# PCB-E21-CMB6_v11-16.net
KiCad netlist of a schematic drawn in EAGLE
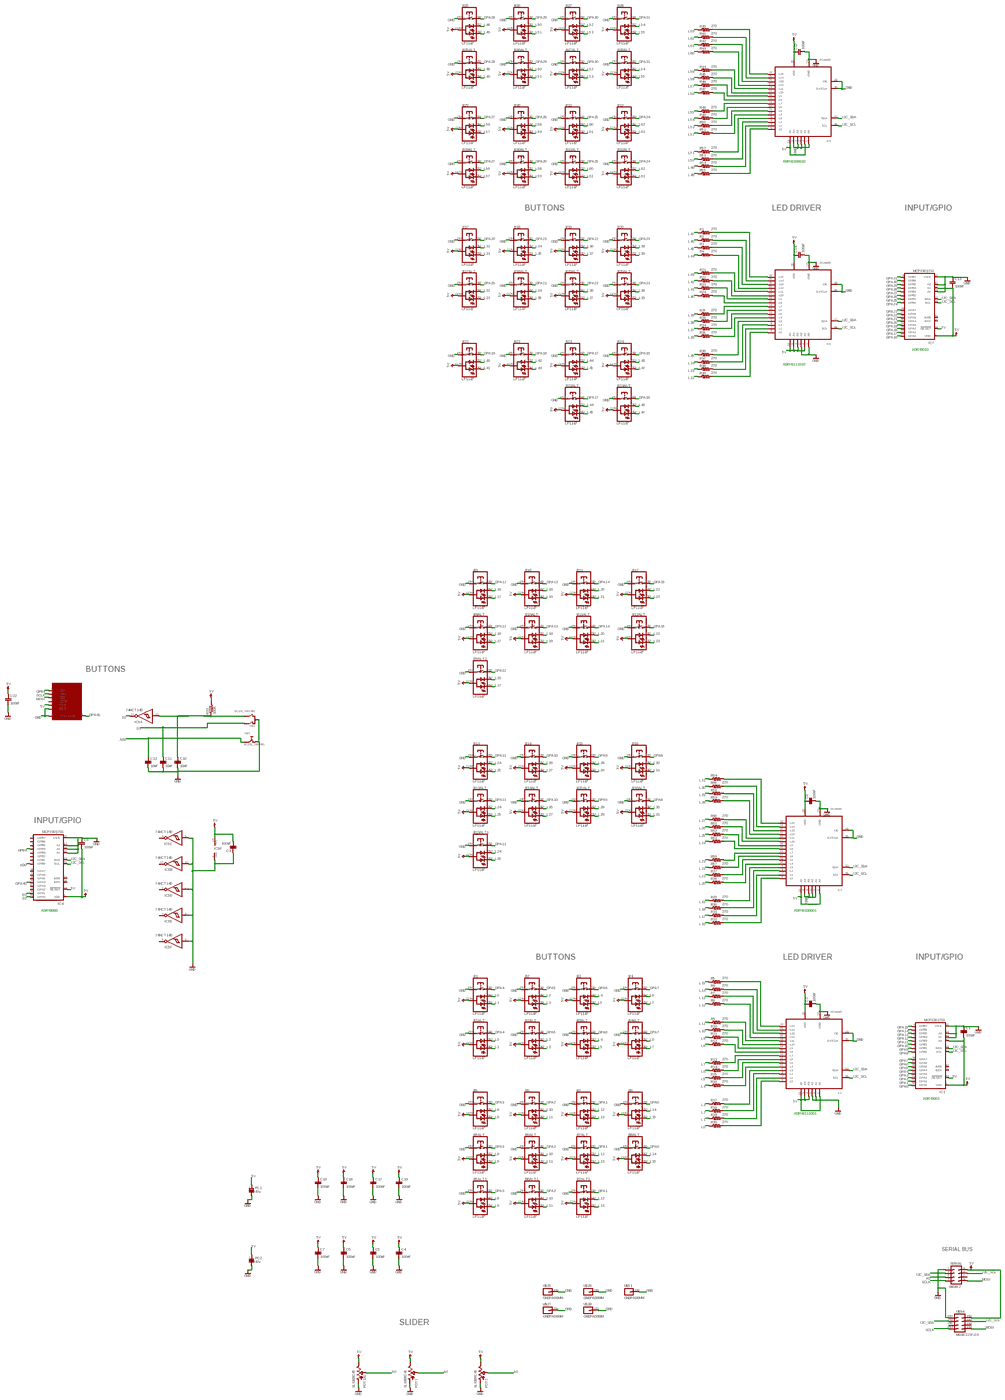
[diagram p0: schematic, sheet 1, overview]
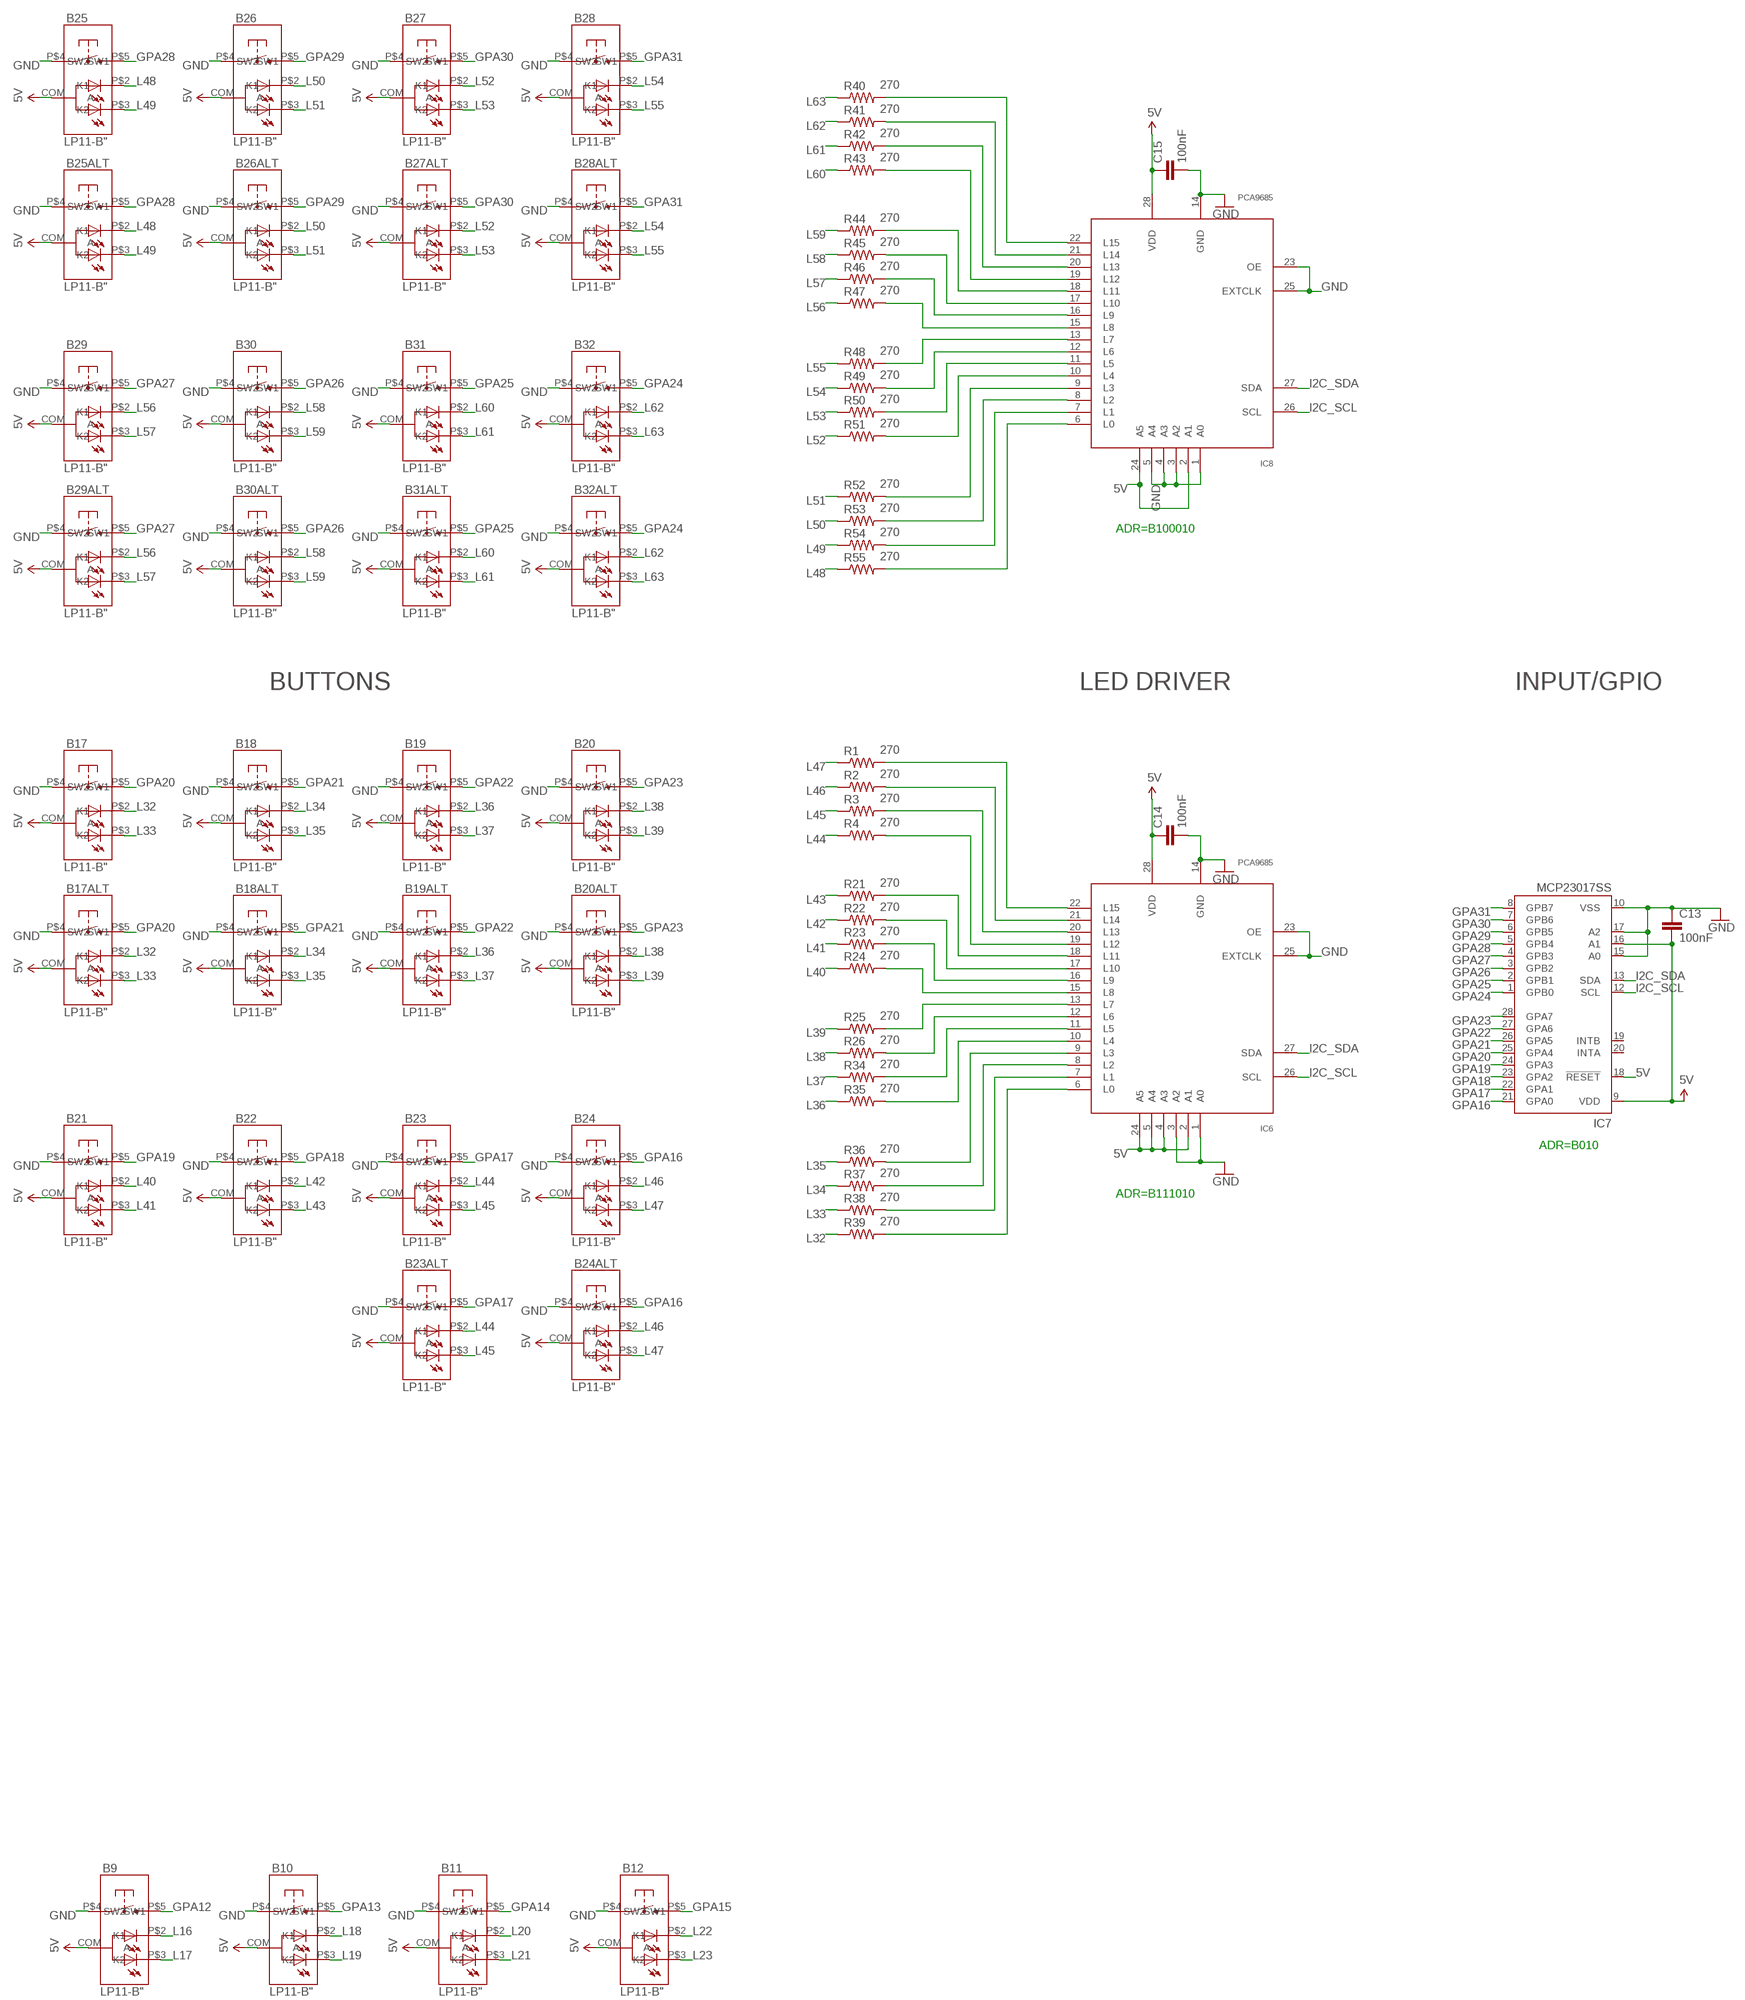
[diagram p1: schematic, sheet 1, part 1 of 5]
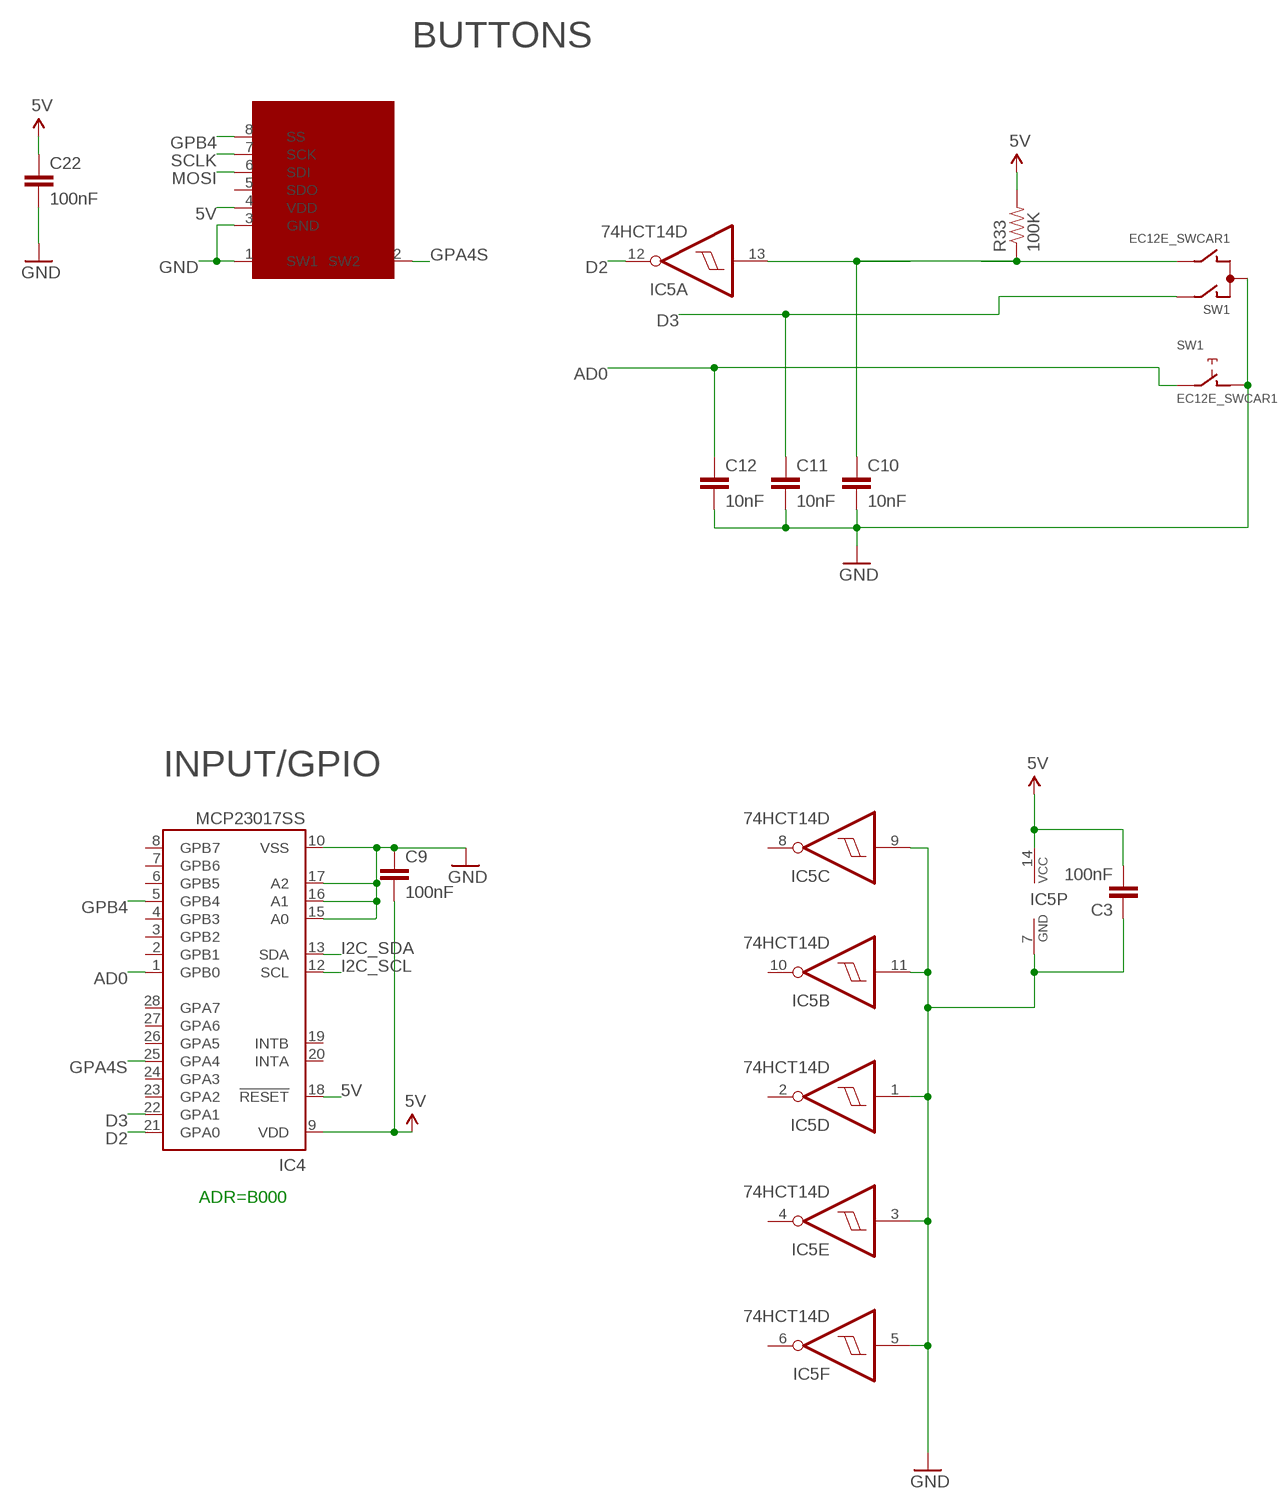
[diagram p2: schematic, sheet 1, part 2 of 5]
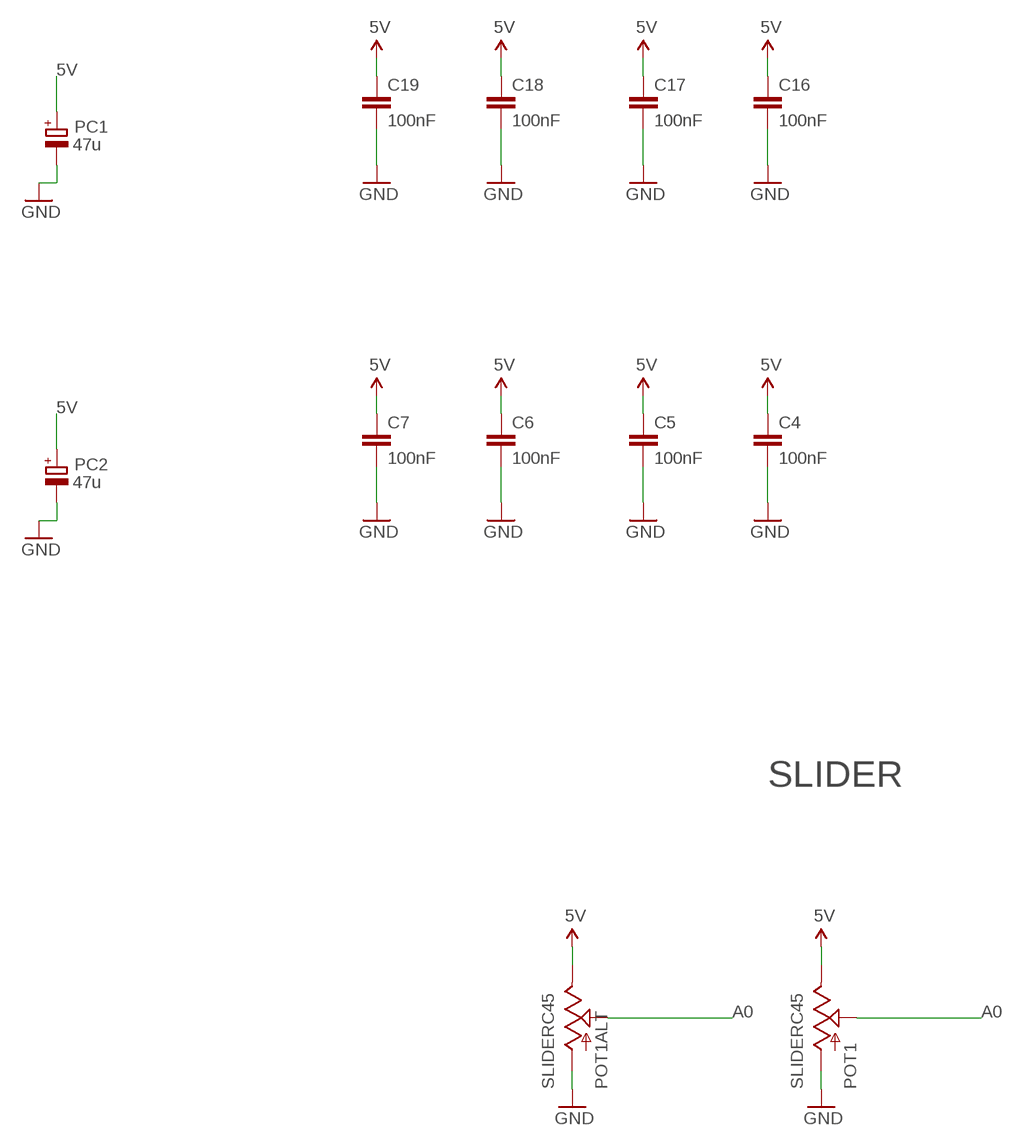
[diagram p3: schematic, sheet 1, part 3 of 5]
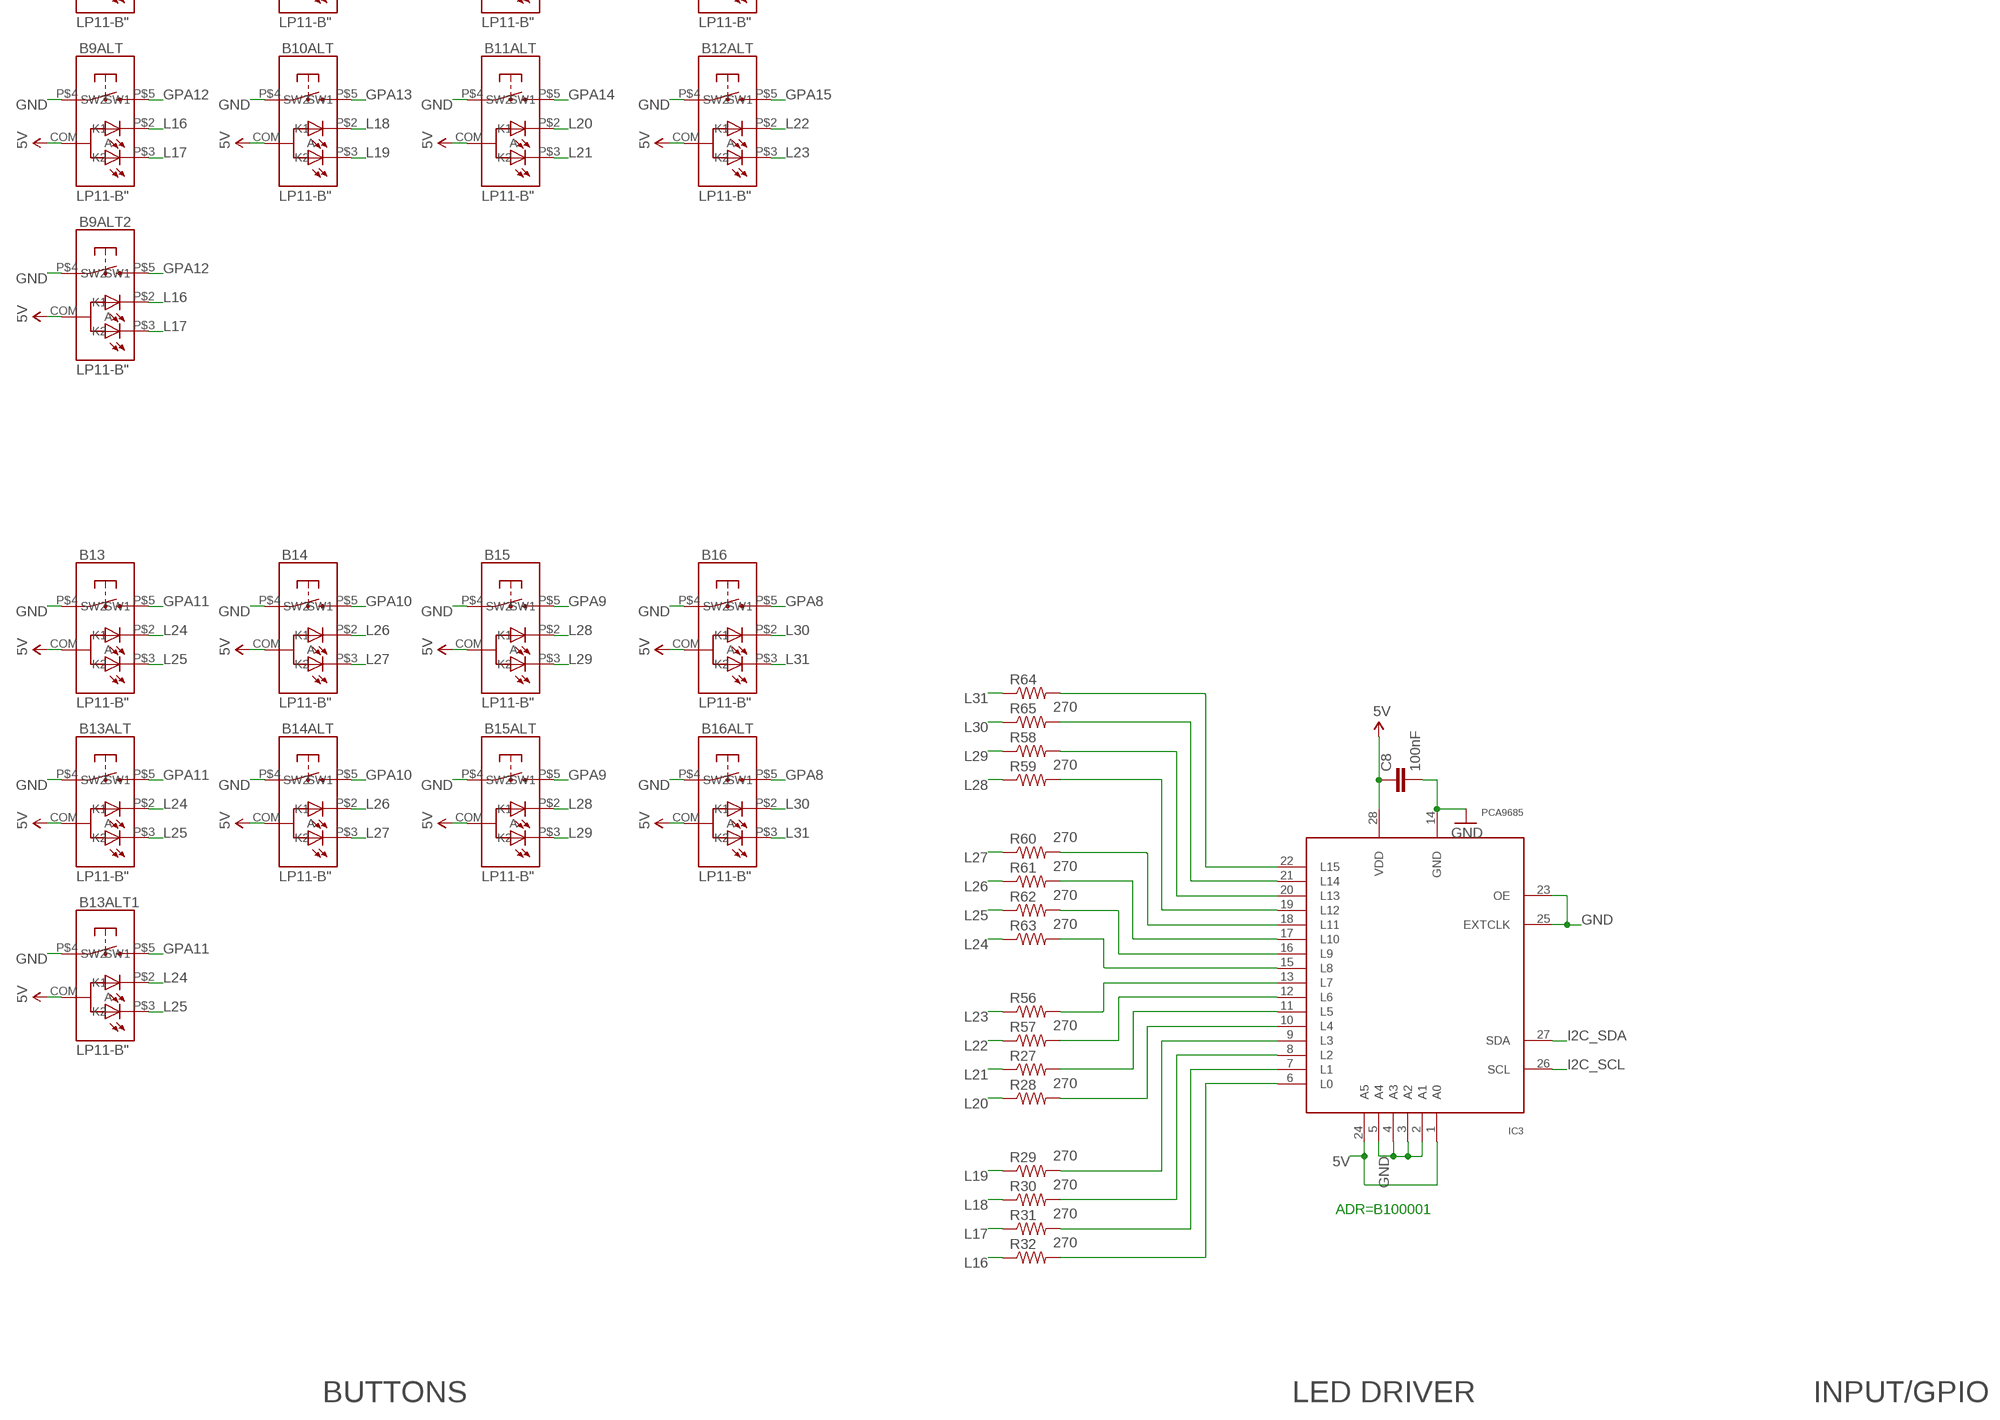
[diagram p4: schematic, sheet 1, part 4 of 5]
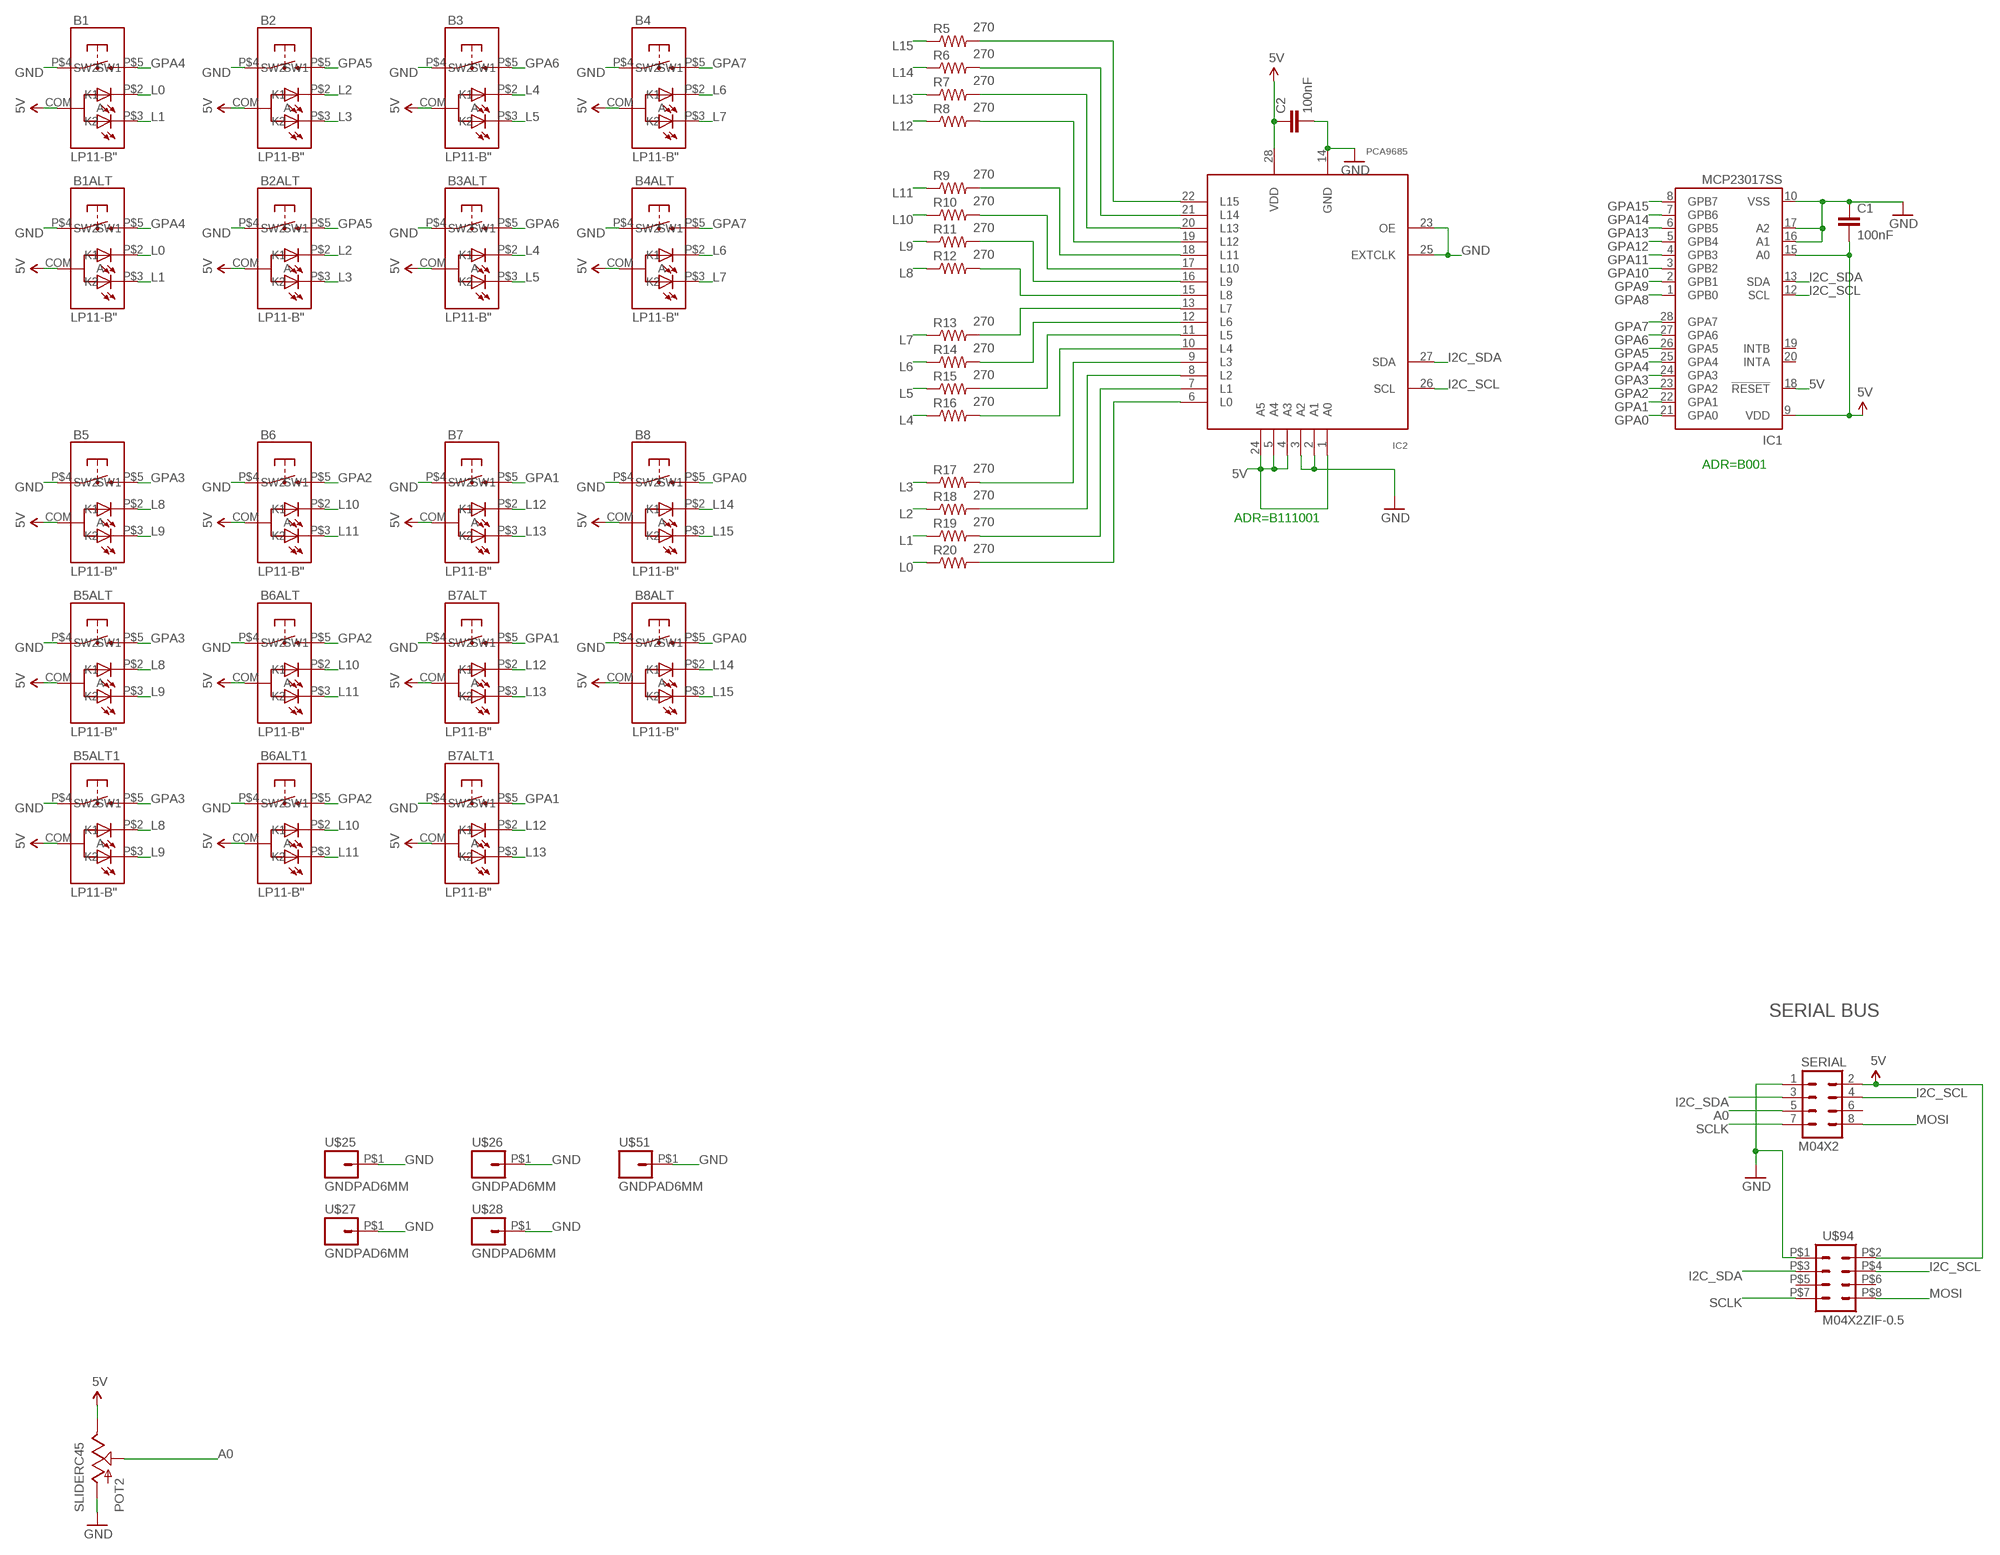
[diagram p5: schematic, sheet 1, part 5 of 5]

(export (version "E")
  (design (tool "Eeschema 10.0.6"))
  (components
    (comp (ref "B1")
      (value "LP11-B\"")
      (footprint "eagle-import:LP11")
      (libsource (lib "eagle-import") (part "LP11-B{dblquote}"))
    )
    (comp (ref "B1ALT")
      (value "LP11-B\"")
      (footprint "eagle-import:LP11")
      (libsource (lib "eagle-import") (part "LP11-B{dblquote}"))
    )
    (comp (ref "B2")
      (value "LP11-B\"")
      (footprint "eagle-import:LP11")
      (libsource (lib "eagle-import") (part "LP11-B{dblquote}"))
    )
    (comp (ref "B2ALT")
      (value "LP11-B\"")
      (footprint "eagle-import:LP11")
      (libsource (lib "eagle-import") (part "LP11-B{dblquote}"))
    )
    (comp (ref "B3")
      (value "LP11-B\"")
      (footprint "eagle-import:LP11")
      (libsource (lib "eagle-import") (part "LP11-B{dblquote}"))
    )
    (comp (ref "B3ALT")
      (value "LP11-B\"")
      (footprint "eagle-import:LP11")
      (libsource (lib "eagle-import") (part "LP11-B{dblquote}"))
    )
    (comp (ref "B4")
      (value "LP11-B\"")
      (footprint "eagle-import:LP11")
      (libsource (lib "eagle-import") (part "LP11-B{dblquote}"))
    )
    (comp (ref "B4ALT")
      (value "LP11-B\"")
      (footprint "eagle-import:LP11")
      (libsource (lib "eagle-import") (part "LP11-B{dblquote}"))
    )
    (comp (ref "B5")
      (value "LP11-B\"")
      (footprint "eagle-import:LP11")
      (libsource (lib "eagle-import") (part "LP11-B{dblquote}"))
    )
    (comp (ref "B5ALT")
      (value "LP11-B\"")
      (footprint "eagle-import:LP11")
      (libsource (lib "eagle-import") (part "LP11-B{dblquote}"))
    )
    (comp (ref "B5ALT1")
      (value "LP11-B\"")
      (footprint "eagle-import:LP11")
      (libsource (lib "eagle-import") (part "LP11-B{dblquote}"))
    )
    (comp (ref "B6")
      (value "LP11-B\"")
      (footprint "eagle-import:LP11")
      (libsource (lib "eagle-import") (part "LP11-B{dblquote}"))
    )
    (comp (ref "B6ALT")
      (value "LP11-B\"")
      (footprint "eagle-import:LP11")
      (libsource (lib "eagle-import") (part "LP11-B{dblquote}"))
    )
    (comp (ref "B6ALT1")
      (value "LP11-B\"")
      (footprint "eagle-import:LP11")
      (libsource (lib "eagle-import") (part "LP11-B{dblquote}"))
    )
    (comp (ref "B7")
      (value "LP11-B\"")
      (footprint "eagle-import:LP11")
      (libsource (lib "eagle-import") (part "LP11-B{dblquote}"))
    )
    (comp (ref "B7ALT")
      (value "LP11-B\"")
      (footprint "eagle-import:LP11")
      (libsource (lib "eagle-import") (part "LP11-B{dblquote}"))
    )
    (comp (ref "B7ALT1")
      (value "LP11-B\"")
      (footprint "eagle-import:LP11")
      (libsource (lib "eagle-import") (part "LP11-B{dblquote}"))
    )
    (comp (ref "B8")
      (value "LP11-B\"")
      (footprint "eagle-import:LP11")
      (libsource (lib "eagle-import") (part "LP11-B{dblquote}"))
    )
    (comp (ref "B8ALT")
      (value "LP11-B\"")
      (footprint "eagle-import:LP11")
      (libsource (lib "eagle-import") (part "LP11-B{dblquote}"))
    )
    (comp (ref "B9")
      (value "LP11-B\"")
      (footprint "eagle-import:LP11")
      (libsource (lib "eagle-import") (part "LP11-B{dblquote}"))
    )
    (comp (ref "B9ALT")
      (value "LP11-B\"")
      (footprint "eagle-import:LP11")
      (libsource (lib "eagle-import") (part "LP11-B{dblquote}"))
    )
    (comp (ref "B9ALT2")
      (value "LP11-B\"")
      (footprint "eagle-import:LP11")
      (libsource (lib "eagle-import") (part "LP11-B{dblquote}"))
    )
    (comp (ref "B10")
      (value "LP11-B\"")
      (footprint "eagle-import:LP11")
      (libsource (lib "eagle-import") (part "LP11-B{dblquote}"))
    )
    (comp (ref "B10ALT")
      (value "LP11-B\"")
      (footprint "eagle-import:LP11")
      (libsource (lib "eagle-import") (part "LP11-B{dblquote}"))
    )
    (comp (ref "B11")
      (value "LP11-B\"")
      (footprint "eagle-import:LP11")
      (libsource (lib "eagle-import") (part "LP11-B{dblquote}"))
    )
    (comp (ref "B11ALT")
      (value "LP11-B\"")
      (footprint "eagle-import:LP11")
      (libsource (lib "eagle-import") (part "LP11-B{dblquote}"))
    )
    (comp (ref "B12")
      (value "LP11-B\"")
      (footprint "eagle-import:LP11")
      (libsource (lib "eagle-import") (part "LP11-B{dblquote}"))
    )
    (comp (ref "B12ALT")
      (value "LP11-B\"")
      (footprint "eagle-import:LP11")
      (libsource (lib "eagle-import") (part "LP11-B{dblquote}"))
    )
    (comp (ref "B13")
      (value "LP11-B\"")
      (footprint "eagle-import:LP11")
      (libsource (lib "eagle-import") (part "LP11-B{dblquote}"))
    )
    (comp (ref "B13ALT")
      (value "LP11-B\"")
      (footprint "eagle-import:LP11")
      (libsource (lib "eagle-import") (part "LP11-B{dblquote}"))
    )
    (comp (ref "B13ALT1")
      (value "LP11-B\"")
      (footprint "eagle-import:LP11")
      (libsource (lib "eagle-import") (part "LP11-B{dblquote}"))
    )
    (comp (ref "B14")
      (value "LP11-B\"")
      (footprint "eagle-import:LP11")
      (libsource (lib "eagle-import") (part "LP11-B{dblquote}"))
    )
    (comp (ref "B14ALT")
      (value "LP11-B\"")
      (footprint "eagle-import:LP11")
      (libsource (lib "eagle-import") (part "LP11-B{dblquote}"))
    )
    (comp (ref "B15")
      (value "LP11-B\"")
      (footprint "eagle-import:LP11")
      (libsource (lib "eagle-import") (part "LP11-B{dblquote}"))
    )
    (comp (ref "B15ALT")
      (value "LP11-B\"")
      (footprint "eagle-import:LP11")
      (libsource (lib "eagle-import") (part "LP11-B{dblquote}"))
    )
    (comp (ref "B16")
      (value "LP11-B\"")
      (footprint "eagle-import:LP11")
      (libsource (lib "eagle-import") (part "LP11-B{dblquote}"))
    )
    (comp (ref "B16ALT")
      (value "LP11-B\"")
      (footprint "eagle-import:LP11")
      (libsource (lib "eagle-import") (part "LP11-B{dblquote}"))
    )
    (comp (ref "B17")
      (value "LP11-B\"")
      (footprint "eagle-import:LP11")
      (libsource (lib "eagle-import") (part "LP11-B{dblquote}"))
    )
    (comp (ref "B17ALT")
      (value "LP11-B\"")
      (footprint "eagle-import:LP11")
      (libsource (lib "eagle-import") (part "LP11-B{dblquote}"))
    )
    (comp (ref "B18")
      (value "LP11-B\"")
      (footprint "eagle-import:LP11")
      (libsource (lib "eagle-import") (part "LP11-B{dblquote}"))
    )
    (comp (ref "B18ALT")
      (value "LP11-B\"")
      (footprint "eagle-import:LP11")
      (libsource (lib "eagle-import") (part "LP11-B{dblquote}"))
    )
    (comp (ref "B19")
      (value "LP11-B\"")
      (footprint "eagle-import:LP11")
      (libsource (lib "eagle-import") (part "LP11-B{dblquote}"))
    )
    (comp (ref "B19ALT")
      (value "LP11-B\"")
      (footprint "eagle-import:LP11")
      (libsource (lib "eagle-import") (part "LP11-B{dblquote}"))
    )
    (comp (ref "B20")
      (value "LP11-B\"")
      (footprint "eagle-import:LP11")
      (libsource (lib "eagle-import") (part "LP11-B{dblquote}"))
    )
    (comp (ref "B20ALT")
      (value "LP11-B\"")
      (footprint "eagle-import:LP11")
      (libsource (lib "eagle-import") (part "LP11-B{dblquote}"))
    )
    (comp (ref "B21")
      (value "LP11-B\"")
      (footprint "eagle-import:LP11")
      (libsource (lib "eagle-import") (part "LP11-B{dblquote}"))
    )
    (comp (ref "B22")
      (value "LP11-B\"")
      (footprint "eagle-import:LP11")
      (libsource (lib "eagle-import") (part "LP11-B{dblquote}"))
    )
    (comp (ref "B23")
      (value "LP11-B\"")
      (footprint "eagle-import:LP11")
      (libsource (lib "eagle-import") (part "LP11-B{dblquote}"))
    )
    (comp (ref "B23ALT")
      (value "LP11-B\"")
      (footprint "eagle-import:LP11")
      (libsource (lib "eagle-import") (part "LP11-B{dblquote}"))
    )
    (comp (ref "B24")
      (value "LP11-B\"")
      (footprint "eagle-import:LP11")
      (libsource (lib "eagle-import") (part "LP11-B{dblquote}"))
    )
    (comp (ref "B24ALT")
      (value "LP11-B\"")
      (footprint "eagle-import:LP11")
      (libsource (lib "eagle-import") (part "LP11-B{dblquote}"))
    )
    (comp (ref "B25")
      (value "LP11-B\"")
      (footprint "eagle-import:LP11")
      (libsource (lib "eagle-import") (part "LP11-B{dblquote}"))
    )
    (comp (ref "B25ALT")
      (value "LP11-B\"")
      (footprint "eagle-import:LP11")
      (libsource (lib "eagle-import") (part "LP11-B{dblquote}"))
    )
    (comp (ref "B26")
      (value "LP11-B\"")
      (footprint "eagle-import:LP11")
      (libsource (lib "eagle-import") (part "LP11-B{dblquote}"))
    )
    (comp (ref "B26ALT")
      (value "LP11-B\"")
      (footprint "eagle-import:LP11")
      (libsource (lib "eagle-import") (part "LP11-B{dblquote}"))
    )
    (comp (ref "B27")
      (value "LP11-B\"")
      (footprint "eagle-import:LP11")
      (libsource (lib "eagle-import") (part "LP11-B{dblquote}"))
    )
    (comp (ref "B27ALT")
      (value "LP11-B\"")
      (footprint "eagle-import:LP11")
      (libsource (lib "eagle-import") (part "LP11-B{dblquote}"))
    )
    (comp (ref "B28")
      (value "LP11-B\"")
      (footprint "eagle-import:LP11")
      (libsource (lib "eagle-import") (part "LP11-B{dblquote}"))
    )
    (comp (ref "B28ALT")
      (value "LP11-B\"")
      (footprint "eagle-import:LP11")
      (libsource (lib "eagle-import") (part "LP11-B{dblquote}"))
    )
    (comp (ref "B29")
      (value "LP11-B\"")
      (footprint "eagle-import:LP11")
      (libsource (lib "eagle-import") (part "LP11-B{dblquote}"))
    )
    (comp (ref "B29ALT")
      (value "LP11-B\"")
      (footprint "eagle-import:LP11")
      (libsource (lib "eagle-import") (part "LP11-B{dblquote}"))
    )
    (comp (ref "B30")
      (value "LP11-B\"")
      (footprint "eagle-import:LP11")
      (libsource (lib "eagle-import") (part "LP11-B{dblquote}"))
    )
    (comp (ref "B30ALT")
      (value "LP11-B\"")
      (footprint "eagle-import:LP11")
      (libsource (lib "eagle-import") (part "LP11-B{dblquote}"))
    )
    (comp (ref "B31")
      (value "LP11-B\"")
      (footprint "eagle-import:LP11")
      (libsource (lib "eagle-import") (part "LP11-B{dblquote}"))
    )
    (comp (ref "B31ALT")
      (value "LP11-B\"")
      (footprint "eagle-import:LP11")
      (libsource (lib "eagle-import") (part "LP11-B{dblquote}"))
    )
    (comp (ref "B32")
      (value "LP11-B\"")
      (footprint "eagle-import:LP11")
      (libsource (lib "eagle-import") (part "LP11-B{dblquote}"))
    )
    (comp (ref "B32ALT")
      (value "LP11-B\"")
      (footprint "eagle-import:LP11")
      (libsource (lib "eagle-import") (part "LP11-B{dblquote}"))
    )
    (comp (ref "C1")
      (value "100nF")
      (footprint "eagle-import:0603-CAP")
      (libsource (lib "eagle-import") (part "CAP0603-CAP"))
    )
    (comp (ref "C2")
      (value "100nF")
      (footprint "eagle-import:0603-CAP")
      (libsource (lib "eagle-import") (part "CAP0603-CAP"))
    )
    (comp (ref "C3")
      (value "100nF")
      (footprint "eagle-import:0603-CAP")
      (libsource (lib "eagle-import") (part "CAP0603-CAP"))
    )
    (comp (ref "C4")
      (value "100nF")
      (footprint "eagle-import:0603-CAP")
      (libsource (lib "eagle-import") (part "CAP0603-CAP"))
    )
    (comp (ref "C5")
      (value "100nF")
      (footprint "eagle-import:0603-CAP")
      (libsource (lib "eagle-import") (part "CAP0603-CAP"))
    )
    (comp (ref "C6")
      (value "100nF")
      (footprint "eagle-import:0603-CAP")
      (libsource (lib "eagle-import") (part "CAP0603-CAP"))
    )
    (comp (ref "C7")
      (value "100nF")
      (footprint "eagle-import:0603-CAP")
      (libsource (lib "eagle-import") (part "CAP0603-CAP"))
    )
    (comp (ref "C8")
      (value "100nF")
      (footprint "eagle-import:0603-CAP")
      (libsource (lib "eagle-import") (part "CAP0603-CAP"))
    )
    (comp (ref "C9")
      (value "100nF")
      (footprint "eagle-import:0603-CAP")
      (libsource (lib "eagle-import") (part "CAP0603-CAP"))
    )
    (comp (ref "C10")
      (value "10nF")
      (footprint "eagle-import:0603-CAP")
      (libsource (lib "eagle-import") (part "CAP0603-CAP"))
    )
    (comp (ref "C11")
      (value "10nF")
      (footprint "eagle-import:0603-CAP")
      (libsource (lib "eagle-import") (part "CAP0603-CAP"))
    )
    (comp (ref "C12")
      (value "10nF")
      (footprint "eagle-import:0603-CAP")
      (libsource (lib "eagle-import") (part "CAP0603-CAP"))
    )
    (comp (ref "C13")
      (value "100nF")
      (footprint "eagle-import:0603-CAP")
      (libsource (lib "eagle-import") (part "CAP0603-CAP"))
    )
    (comp (ref "C14")
      (value "100nF")
      (footprint "eagle-import:0603-CAP")
      (libsource (lib "eagle-import") (part "CAP0603-CAP"))
    )
    (comp (ref "C15")
      (value "100nF")
      (footprint "eagle-import:0603-CAP")
      (libsource (lib "eagle-import") (part "CAP0603-CAP"))
    )
    (comp (ref "C16")
      (value "100nF")
      (footprint "eagle-import:0603-CAP")
      (libsource (lib "eagle-import") (part "CAP0603-CAP"))
    )
    (comp (ref "C17")
      (value "100nF")
      (footprint "eagle-import:0603-CAP")
      (libsource (lib "eagle-import") (part "CAP0603-CAP"))
    )
    (comp (ref "C18")
      (value "100nF")
      (footprint "eagle-import:0603-CAP")
      (libsource (lib "eagle-import") (part "CAP0603-CAP"))
    )
    (comp (ref "C19")
      (value "100nF")
      (footprint "eagle-import:0603-CAP")
      (libsource (lib "eagle-import") (part "CAP0603-CAP"))
    )
    (comp (ref "C22")
      (value "100nF")
      (footprint "eagle-import:0603-CAP")
      (libsource (lib "eagle-import") (part "CAP0603-CAP"))
    )
    (comp (ref "IC1")
      (value "MCP23017SS")
      (footprint "eagle-import:SSOP28")
      (fields
        (field (name "MF") "MICROCHIP")
        (field (name "MPN") "MCP23017-E/SS")
        (field (name "MPN_1") "MCP23017-E/SS")
        (field (name "OC_FARNELL") "1467674")
        (field (name "OC_NEWARK") "31K2960")
      )
      (libsource (lib "eagle-import") (part "MCP23017SS"))
    )
    (comp (ref "IC2")
      (value "PCA9685")
      (footprint "eagle-import:TSSOP28")
      (libsource (lib "eagle-import") (part "PCA9685"))
    )
    (comp (ref "IC3")
      (value "PCA9685")
      (footprint "eagle-import:TSSOP28")
      (libsource (lib "eagle-import") (part "PCA9685"))
    )
    (comp (ref "IC4")
      (value "MCP23017SS")
      (footprint "eagle-import:SSOP28")
      (fields
        (field (name "MF") "MICROCHIP")
        (field (name "MPN") "MCP23017-E/SS")
        (field (name "MPN_1") "MCP23017-E/SS")
        (field (name "OC_FARNELL") "1467674")
        (field (name "OC_NEWARK") "31K2960")
      )
      (libsource (lib "eagle-import") (part "MCP23017SS"))
    )
    (comp (ref "IC5")
      (value "74HCT14D")
      (footprint "eagle-import:SO14")
      (libsource (lib "eagle-import") (part "7414DHCT"))
    )
    (comp (ref "IC6")
      (value "PCA9685")
      (footprint "eagle-import:TSSOP28")
      (libsource (lib "eagle-import") (part "PCA9685"))
    )
    (comp (ref "IC7")
      (value "MCP23017SS")
      (footprint "eagle-import:SSOP28")
      (fields
        (field (name "MF") "MICROCHIP")
        (field (name "MPN") "MCP23017-E/SS")
        (field (name "MPN_1") "MCP23017-E/SS")
        (field (name "OC_FARNELL") "1467674")
        (field (name "OC_NEWARK") "31K2960")
      )
      (libsource (lib "eagle-import") (part "MCP23017SS"))
    )
    (comp (ref "IC8")
      (value "PCA9685")
      (footprint "eagle-import:TSSOP28")
      (libsource (lib "eagle-import") (part "PCA9685"))
    )
    (comp (ref "PC1")
      (value "47u")
      (footprint "eagle-import:PANASONIC_D")
      (libsource (lib "eagle-import") (part "CPOL-EUD"))
    )
    (comp (ref "PC2")
      (value "47u")
      (footprint "eagle-import:PANASONIC_D")
      (libsource (lib "eagle-import") (part "CPOL-EUD"))
    )
    (comp (ref "POT1")
      (value "SLIDERC45")
      (footprint "eagle-import:SLIDER45-CAR1")
      (libsource (lib "eagle-import") (part "SLIDERC45"))
    )
    (comp (ref "POT1ALT")
      (value "SLIDERC45")
      (footprint "eagle-import:SLIDER45-CAR1")
      (libsource (lib "eagle-import") (part "SLIDERC45"))
    )
    (comp (ref "POT2")
      (value "SLIDERC45")
      (footprint "eagle-import:SLIDER45-CAR1")
      (libsource (lib "eagle-import") (part "SLIDERC45"))
    )
    (comp (ref "R1")
      (value "270")
      (footprint "eagle-import:0603-RES")
      (libsource (lib "eagle-import") (part "RESISTOR0603-RES"))
    )
    (comp (ref "R2")
      (value "270")
      (footprint "eagle-import:0603-RES")
      (libsource (lib "eagle-import") (part "RESISTOR0603-RES"))
    )
    (comp (ref "R3")
      (value "270")
      (footprint "eagle-import:0603-RES")
      (libsource (lib "eagle-import") (part "RESISTOR0603-RES"))
    )
    (comp (ref "R4")
      (value "270")
      (footprint "eagle-import:0603-RES")
      (libsource (lib "eagle-import") (part "RESISTOR0603-RES"))
    )
    (comp (ref "R5")
      (value "270")
      (footprint "eagle-import:0603-RES")
      (libsource (lib "eagle-import") (part "RESISTOR0603-RES"))
    )
    (comp (ref "R6")
      (value "270")
      (footprint "eagle-import:0603-RES")
      (libsource (lib "eagle-import") (part "RESISTOR0603-RES"))
    )
    (comp (ref "R7")
      (value "270")
      (footprint "eagle-import:0603-RES")
      (libsource (lib "eagle-import") (part "RESISTOR0603-RES"))
    )
    (comp (ref "R8")
      (value "270")
      (footprint "eagle-import:0603-RES")
      (libsource (lib "eagle-import") (part "RESISTOR0603-RES"))
    )
    (comp (ref "R9")
      (value "270")
      (footprint "eagle-import:0603-RES")
      (libsource (lib "eagle-import") (part "RESISTOR0603-RES"))
    )
    (comp (ref "R10")
      (value "270")
      (footprint "eagle-import:0603-RES")
      (libsource (lib "eagle-import") (part "RESISTOR0603-RES"))
    )
    (comp (ref "R11")
      (value "270")
      (footprint "eagle-import:0603-RES")
      (libsource (lib "eagle-import") (part "RESISTOR0603-RES"))
    )
    (comp (ref "R12")
      (value "270")
      (footprint "eagle-import:0603-RES")
      (libsource (lib "eagle-import") (part "RESISTOR0603-RES"))
    )
    (comp (ref "R13")
      (value "270")
      (footprint "eagle-import:0603-RES")
      (libsource (lib "eagle-import") (part "RESISTOR0603-RES"))
    )
    (comp (ref "R14")
      (value "270")
      (footprint "eagle-import:0603-RES")
      (libsource (lib "eagle-import") (part "RESISTOR0603-RES"))
    )
    (comp (ref "R15")
      (value "270")
      (footprint "eagle-import:0603-RES")
      (libsource (lib "eagle-import") (part "RESISTOR0603-RES"))
    )
    (comp (ref "R16")
      (value "270")
      (footprint "eagle-import:0603-RES")
      (libsource (lib "eagle-import") (part "RESISTOR0603-RES"))
    )
    (comp (ref "R17")
      (value "270")
      (footprint "eagle-import:0603-RES")
      (libsource (lib "eagle-import") (part "RESISTOR0603-RES"))
    )
    (comp (ref "R18")
      (value "270")
      (footprint "eagle-import:0603-RES")
      (libsource (lib "eagle-import") (part "RESISTOR0603-RES"))
    )
    (comp (ref "R19")
      (value "270")
      (footprint "eagle-import:0603-RES")
      (libsource (lib "eagle-import") (part "RESISTOR0603-RES"))
    )
    (comp (ref "R20")
      (value "270")
      (footprint "eagle-import:0603-RES")
      (libsource (lib "eagle-import") (part "RESISTOR0603-RES"))
    )
    (comp (ref "R21")
      (value "270")
      (footprint "eagle-import:0603-RES")
      (libsource (lib "eagle-import") (part "RESISTOR0603-RES"))
    )
    (comp (ref "R22")
      (value "270")
      (footprint "eagle-import:0603-RES")
      (libsource (lib "eagle-import") (part "RESISTOR0603-RES"))
    )
    (comp (ref "R23")
      (value "270")
      (footprint "eagle-import:0603-RES")
      (libsource (lib "eagle-import") (part "RESISTOR0603-RES"))
    )
    (comp (ref "R24")
      (value "270")
      (footprint "eagle-import:0603-RES")
      (libsource (lib "eagle-import") (part "RESISTOR0603-RES"))
    )
    (comp (ref "R25")
      (value "270")
      (footprint "eagle-import:0603-RES")
      (libsource (lib "eagle-import") (part "RESISTOR0603-RES"))
    )
    (comp (ref "R26")
      (value "270")
      (footprint "eagle-import:0603-RES")
      (libsource (lib "eagle-import") (part "RESISTOR0603-RES"))
    )
    (comp (ref "R27")
      (value "270")
      (footprint "eagle-import:0603-RES")
      (libsource (lib "eagle-import") (part "RESISTOR0603-RES"))
    )
    (comp (ref "R28")
      (value "270")
      (footprint "eagle-import:0603-RES")
      (libsource (lib "eagle-import") (part "RESISTOR0603-RES"))
    )
    (comp (ref "R29")
      (value "270")
      (footprint "eagle-import:0603-RES")
      (libsource (lib "eagle-import") (part "RESISTOR0603-RES"))
    )
    (comp (ref "R30")
      (value "270")
      (footprint "eagle-import:0603-RES")
      (libsource (lib "eagle-import") (part "RESISTOR0603-RES"))
    )
    (comp (ref "R31")
      (value "270")
      (footprint "eagle-import:0603-RES")
      (libsource (lib "eagle-import") (part "RESISTOR0603-RES"))
    )
    (comp (ref "R32")
      (value "270")
      (footprint "eagle-import:0603-RES")
      (libsource (lib "eagle-import") (part "RESISTOR0603-RES"))
    )
    (comp (ref "R33")
      (value "100K")
      (footprint "eagle-import:0603-RES")
      (libsource (lib "eagle-import") (part "RESISTOR0603-RES"))
    )
    (comp (ref "R34")
      (value "270")
      (footprint "eagle-import:0603-RES")
      (libsource (lib "eagle-import") (part "RESISTOR0603-RES"))
    )
    (comp (ref "R35")
      (value "270")
      (footprint "eagle-import:0603-RES")
      (libsource (lib "eagle-import") (part "RESISTOR0603-RES"))
    )
    (comp (ref "R36")
      (value "270")
      (footprint "eagle-import:0603-RES")
      (libsource (lib "eagle-import") (part "RESISTOR0603-RES"))
    )
    (comp (ref "R37")
      (value "270")
      (footprint "eagle-import:0603-RES")
      (libsource (lib "eagle-import") (part "RESISTOR0603-RES"))
    )
    (comp (ref "R38")
      (value "270")
      (footprint "eagle-import:0603-RES")
      (libsource (lib "eagle-import") (part "RESISTOR0603-RES"))
    )
    (comp (ref "R39")
      (value "270")
      (footprint "eagle-import:0603-RES")
      (libsource (lib "eagle-import") (part "RESISTOR0603-RES"))
    )
    (comp (ref "R40")
      (value "270")
      (footprint "eagle-import:0603-RES")
      (libsource (lib "eagle-import") (part "RESISTOR0603-RES"))
    )
    (comp (ref "R41")
      (value "270")
      (footprint "eagle-import:0603-RES")
      (libsource (lib "eagle-import") (part "RESISTOR0603-RES"))
    )
    (comp (ref "R42")
      (value "270")
      (footprint "eagle-import:0603-RES")
      (libsource (lib "eagle-import") (part "RESISTOR0603-RES"))
    )
    (comp (ref "R43")
      (value "270")
      (footprint "eagle-import:0603-RES")
      (libsource (lib "eagle-import") (part "RESISTOR0603-RES"))
    )
    (comp (ref "R44")
      (value "270")
      (footprint "eagle-import:0603-RES")
      (libsource (lib "eagle-import") (part "RESISTOR0603-RES"))
    )
    (comp (ref "R45")
      (value "270")
      (footprint "eagle-import:0603-RES")
      (libsource (lib "eagle-import") (part "RESISTOR0603-RES"))
    )
    (comp (ref "R46")
      (value "270")
      (footprint "eagle-import:0603-RES")
      (libsource (lib "eagle-import") (part "RESISTOR0603-RES"))
    )
    (comp (ref "R47")
      (value "270")
      (footprint "eagle-import:0603-RES")
      (libsource (lib "eagle-import") (part "RESISTOR0603-RES"))
    )
    (comp (ref "R48")
      (value "270")
      (footprint "eagle-import:0603-RES")
      (libsource (lib "eagle-import") (part "RESISTOR0603-RES"))
    )
    (comp (ref "R49")
      (value "270")
      (footprint "eagle-import:0603-RES")
      (libsource (lib "eagle-import") (part "RESISTOR0603-RES"))
    )
    (comp (ref "R50")
      (value "270")
      (footprint "eagle-import:0603-RES")
      (libsource (lib "eagle-import") (part "RESISTOR0603-RES"))
    )
    (comp (ref "R51")
      (value "270")
      (footprint "eagle-import:0603-RES")
      (libsource (lib "eagle-import") (part "RESISTOR0603-RES"))
    )
    (comp (ref "R52")
      (value "270")
      (footprint "eagle-import:0603-RES")
      (libsource (lib "eagle-import") (part "RESISTOR0603-RES"))
    )
    (comp (ref "R53")
      (value "270")
      (footprint "eagle-import:0603-RES")
      (libsource (lib "eagle-import") (part "RESISTOR0603-RES"))
    )
    (comp (ref "R54")
      (value "270")
      (footprint "eagle-import:0603-RES")
      (libsource (lib "eagle-import") (part "RESISTOR0603-RES"))
    )
    (comp (ref "R55")
      (value "270")
      (footprint "eagle-import:0603-RES")
      (libsource (lib "eagle-import") (part "RESISTOR0603-RES"))
    )
    (comp (ref "R56")
      (value "270")
      (footprint "eagle-import:0603-RES")
      (libsource (lib "eagle-import") (part "RESISTOR0603-RES"))
    )
    (comp (ref "R57")
      (value "270")
      (footprint "eagle-import:0603-RES")
      (libsource (lib "eagle-import") (part "RESISTOR0603-RES"))
    )
    (comp (ref "R58")
      (value "270")
      (footprint "eagle-import:0603-RES")
      (libsource (lib "eagle-import") (part "RESISTOR0603-RES"))
    )
    (comp (ref "R59")
      (value "270")
      (footprint "eagle-import:0603-RES")
      (libsource (lib "eagle-import") (part "RESISTOR0603-RES"))
    )
    (comp (ref "R60")
      (value "270")
      (footprint "eagle-import:0603-RES")
      (libsource (lib "eagle-import") (part "RESISTOR0603-RES"))
    )
    (comp (ref "R61")
      (value "270")
      (footprint "eagle-import:0603-RES")
      (libsource (lib "eagle-import") (part "RESISTOR0603-RES"))
    )
    (comp (ref "R62")
      (value "270")
      (footprint "eagle-import:0603-RES")
      (libsource (lib "eagle-import") (part "RESISTOR0603-RES"))
    )
    (comp (ref "R63")
      (value "270")
      (footprint "eagle-import:0603-RES")
      (libsource (lib "eagle-import") (part "RESISTOR0603-RES"))
    )
    (comp (ref "R64")
      (value "270")
      (footprint "eagle-import:0603-RES")
      (libsource (lib "eagle-import") (part "RESISTOR0603-RES"))
    )
    (comp (ref "R65")
      (value "270")
      (footprint "eagle-import:0603-RES")
      (libsource (lib "eagle-import") (part "RESISTOR0603-RES"))
    )
    (comp (ref "SERIAL")
      (value "M04X2")
      (footprint "eagle-import:2X4")
      (libsource (lib "eagle-import") (part "SparkFun_M04X2"))
    )
    (comp (ref "SSW1")
      (value "SMART_SWITCHSMART_SWITCH_8PIN")
      (footprint "eagle-import:SMART_SWITCH")
      (libsource (lib "eagle-import") (part "SMART_SWITCHSMART_SWITCH_8PIN"))
    )
    (comp (ref "SW1")
      (value "EC12E_SWCAR1")
      (footprint "eagle-import:ALPS_EC12E_SW-CAR1")
      (libsource (lib "eagle-import") (part "EC12E_SWCAR1"))
    )
    (comp (ref "U$25")
      (value "GNDPAD6MM")
      (footprint "eagle-import:3.2MMPAD6MM")
      (libsource (lib "eagle-import") (part "GNDPAD6MM"))
    )
    (comp (ref "U$26")
      (value "GNDPAD6MM")
      (footprint "eagle-import:3.2MMPAD6MM")
      (libsource (lib "eagle-import") (part "GNDPAD6MM"))
    )
    (comp (ref "U$27")
      (value "GNDPAD6MM")
      (footprint "eagle-import:3.2MMPAD6MM")
      (libsource (lib "eagle-import") (part "GNDPAD6MM"))
    )
    (comp (ref "U$28")
      (value "GNDPAD6MM")
      (footprint "eagle-import:3.2MMPAD6MM")
      (libsource (lib "eagle-import") (part "GNDPAD6MM"))
    )
    (comp (ref "U$51")
      (value "GNDPAD6MM")
      (footprint "eagle-import:3.2MMPAD6MM")
      (libsource (lib "eagle-import") (part "GNDPAD6MM"))
    )
    (comp (ref "U$94")
      (value "M04X2ZIF-0.5")
      (footprint "eagle-import:ZIP-8-0.5")
      (libsource (lib "eagle-import") (part "M04X2ZIF-0.5"))
    )
  )
  (nets
    (net (code "1") (name "5V") (class "Default")
      (node (ref "B1") (pin "COM") (pinfunction "A_COM") (pintype "bidirectional"))
      (node (ref "B10") (pin "COM") (pinfunction "A_COM") (pintype "bidirectional"))
      (node (ref "B10ALT") (pin "COM") (pinfunction "A_COM") (pintype "bidirectional"))
      (node (ref "B11") (pin "COM") (pinfunction "A_COM") (pintype "bidirectional"))
      (node (ref "B11ALT") (pin "COM") (pinfunction "A_COM") (pintype "bidirectional"))
      (node (ref "B12") (pin "COM") (pinfunction "A_COM") (pintype "bidirectional"))
      (node (ref "B12ALT") (pin "COM") (pinfunction "A_COM") (pintype "bidirectional"))
      (node (ref "B13") (pin "COM") (pinfunction "A_COM") (pintype "bidirectional"))
      (node (ref "B13ALT") (pin "COM") (pinfunction "A_COM") (pintype "bidirectional"))
      (node (ref "B13ALT1") (pin "COM") (pinfunction "A_COM") (pintype "bidirectional"))
      (node (ref "B14") (pin "COM") (pinfunction "A_COM") (pintype "bidirectional"))
      (node (ref "B14ALT") (pin "COM") (pinfunction "A_COM") (pintype "bidirectional"))
      (node (ref "B15") (pin "COM") (pinfunction "A_COM") (pintype "bidirectional"))
      (node (ref "B15ALT") (pin "COM") (pinfunction "A_COM") (pintype "bidirectional"))
      (node (ref "B16") (pin "COM") (pinfunction "A_COM") (pintype "bidirectional"))
      (node (ref "B16ALT") (pin "COM") (pinfunction "A_COM") (pintype "bidirectional"))
      (node (ref "B17") (pin "COM") (pinfunction "A_COM") (pintype "bidirectional"))
      (node (ref "B17ALT") (pin "COM") (pinfunction "A_COM") (pintype "bidirectional"))
      (node (ref "B18") (pin "COM") (pinfunction "A_COM") (pintype "bidirectional"))
      (node (ref "B18ALT") (pin "COM") (pinfunction "A_COM") (pintype "bidirectional"))
      (node (ref "B19") (pin "COM") (pinfunction "A_COM") (pintype "bidirectional"))
      (node (ref "B19ALT") (pin "COM") (pinfunction "A_COM") (pintype "bidirectional"))
      (node (ref "B1ALT") (pin "COM") (pinfunction "A_COM") (pintype "bidirectional"))
      (node (ref "B2") (pin "COM") (pinfunction "A_COM") (pintype "bidirectional"))
      (node (ref "B20") (pin "COM") (pinfunction "A_COM") (pintype "bidirectional"))
      (node (ref "B20ALT") (pin "COM") (pinfunction "A_COM") (pintype "bidirectional"))
      (node (ref "B21") (pin "COM") (pinfunction "A_COM") (pintype "bidirectional"))
      (node (ref "B22") (pin "COM") (pinfunction "A_COM") (pintype "bidirectional"))
      (node (ref "B23") (pin "COM") (pinfunction "A_COM") (pintype "bidirectional"))
      (node (ref "B23ALT") (pin "COM") (pinfunction "A_COM") (pintype "bidirectional"))
      (node (ref "B24") (pin "COM") (pinfunction "A_COM") (pintype "bidirectional"))
      (node (ref "B24ALT") (pin "COM") (pinfunction "A_COM") (pintype "bidirectional"))
      (node (ref "B25") (pin "COM") (pinfunction "A_COM") (pintype "bidirectional"))
      (node (ref "B25ALT") (pin "COM") (pinfunction "A_COM") (pintype "bidirectional"))
      (node (ref "B26") (pin "COM") (pinfunction "A_COM") (pintype "bidirectional"))
      (node (ref "B26ALT") (pin "COM") (pinfunction "A_COM") (pintype "bidirectional"))
      (node (ref "B27") (pin "COM") (pinfunction "A_COM") (pintype "bidirectional"))
      (node (ref "B27ALT") (pin "COM") (pinfunction "A_COM") (pintype "bidirectional"))
      (node (ref "B28") (pin "COM") (pinfunction "A_COM") (pintype "bidirectional"))
      (node (ref "B28ALT") (pin "COM") (pinfunction "A_COM") (pintype "bidirectional"))
      (node (ref "B29") (pin "COM") (pinfunction "A_COM") (pintype "bidirectional"))
      (node (ref "B29ALT") (pin "COM") (pinfunction "A_COM") (pintype "bidirectional"))
      (node (ref "B2ALT") (pin "COM") (pinfunction "A_COM") (pintype "bidirectional"))
      (node (ref "B3") (pin "COM") (pinfunction "A_COM") (pintype "bidirectional"))
      (node (ref "B30") (pin "COM") (pinfunction "A_COM") (pintype "bidirectional"))
      (node (ref "B30ALT") (pin "COM") (pinfunction "A_COM") (pintype "bidirectional"))
      (node (ref "B31") (pin "COM") (pinfunction "A_COM") (pintype "bidirectional"))
      (node (ref "B31ALT") (pin "COM") (pinfunction "A_COM") (pintype "bidirectional"))
      (node (ref "B32") (pin "COM") (pinfunction "A_COM") (pintype "bidirectional"))
      (node (ref "B32ALT") (pin "COM") (pinfunction "A_COM") (pintype "bidirectional"))
      (node (ref "B3ALT") (pin "COM") (pinfunction "A_COM") (pintype "bidirectional"))
      (node (ref "B4") (pin "COM") (pinfunction "A_COM") (pintype "bidirectional"))
      (node (ref "B4ALT") (pin "COM") (pinfunction "A_COM") (pintype "bidirectional"))
      (node (ref "B5") (pin "COM") (pinfunction "A_COM") (pintype "bidirectional"))
      (node (ref "B5ALT") (pin "COM") (pinfunction "A_COM") (pintype "bidirectional"))
      (node (ref "B5ALT1") (pin "COM") (pinfunction "A_COM") (pintype "bidirectional"))
      (node (ref "B6") (pin "COM") (pinfunction "A_COM") (pintype "bidirectional"))
      (node (ref "B6ALT") (pin "COM") (pinfunction "A_COM") (pintype "bidirectional"))
      (node (ref "B6ALT1") (pin "COM") (pinfunction "A_COM") (pintype "bidirectional"))
      (node (ref "B7") (pin "COM") (pinfunction "A_COM") (pintype "bidirectional"))
      (node (ref "B7ALT") (pin "COM") (pinfunction "A_COM") (pintype "bidirectional"))
      (node (ref "B7ALT1") (pin "COM") (pinfunction "A_COM") (pintype "bidirectional"))
      (node (ref "B8") (pin "COM") (pinfunction "A_COM") (pintype "bidirectional"))
      (node (ref "B8ALT") (pin "COM") (pinfunction "A_COM") (pintype "bidirectional"))
      (node (ref "B9") (pin "COM") (pinfunction "A_COM") (pintype "bidirectional"))
      (node (ref "B9ALT") (pin "COM") (pinfunction "A_COM") (pintype "bidirectional"))
      (node (ref "B9ALT2") (pin "COM") (pinfunction "A_COM") (pintype "bidirectional"))
      (node (ref "C1") (pin "2") (pinfunction "2_2") (pintype "passive"))
      (node (ref "C13") (pin "2") (pinfunction "2_2") (pintype "passive"))
      (node (ref "C14") (pin "1") (pinfunction "1_1") (pintype "passive"))
      (node (ref "C15") (pin "1") (pinfunction "1_1") (pintype "passive"))
      (node (ref "C16") (pin "1") (pinfunction "1_1") (pintype "passive"))
      (node (ref "C17") (pin "1") (pinfunction "1_1") (pintype "passive"))
      (node (ref "C18") (pin "1") (pinfunction "1_1") (pintype "passive"))
      (node (ref "C19") (pin "1") (pinfunction "1_1") (pintype "passive"))
      (node (ref "C2") (pin "1") (pinfunction "1_1") (pintype "passive"))
      (node (ref "C22") (pin "1") (pinfunction "1_1") (pintype "passive"))
      (node (ref "C3") (pin "2") (pinfunction "2_2") (pintype "passive"))
      (node (ref "C4") (pin "1") (pinfunction "1_1") (pintype "passive"))
      (node (ref "C5") (pin "1") (pinfunction "1_1") (pintype "passive"))
      (node (ref "C6") (pin "1") (pinfunction "1_1") (pintype "passive"))
      (node (ref "C7") (pin "1") (pinfunction "1_1") (pintype "passive"))
      (node (ref "C8") (pin "1") (pinfunction "1_1") (pintype "passive"))
      (node (ref "C9") (pin "2") (pinfunction "2_2") (pintype "passive"))
      (node (ref "IC1") (pin "15") (pinfunction "A0_15") (pintype "input"))
      (node (ref "IC1") (pin "18") (pinfunction "~{RESET}_18") (pintype "input"))
      (node (ref "IC1") (pin "9") (pinfunction "VDD_9") (pintype "power_in"))
      (node (ref "IC2") (pin "1") (pinfunction "A0_1") (pintype "input"))
      (node (ref "IC2") (pin "24") (pinfunction "A5_24") (pintype "input"))
      (node (ref "IC2") (pin "28") (pinfunction "VDD_28") (pintype "power_in"))
      (node (ref "IC2") (pin "4") (pinfunction "A3_4") (pintype "input"))
      (node (ref "IC2") (pin "5") (pinfunction "A4_5") (pintype "input"))
      (node (ref "IC3") (pin "1") (pinfunction "A0_1") (pintype "input"))
      (node (ref "IC3") (pin "24") (pinfunction "A5_24") (pintype "input"))
      (node (ref "IC3") (pin "28") (pinfunction "VDD_28") (pintype "power_in"))
      (node (ref "IC4") (pin "18") (pinfunction "~{RESET}_18") (pintype "input"))
      (node (ref "IC4") (pin "9") (pinfunction "VDD_9") (pintype "power_in"))
      (node (ref "IC5") (pin "14") (pinfunction "VCC_14") (pintype "power_in"))
      (node (ref "IC6") (pin "2") (pinfunction "A1_2") (pintype "input"))
      (node (ref "IC6") (pin "24") (pinfunction "A5_24") (pintype "input"))
      (node (ref "IC6") (pin "28") (pinfunction "VDD_28") (pintype "power_in"))
      (node (ref "IC6") (pin "4") (pinfunction "A3_4") (pintype "input"))
      (node (ref "IC6") (pin "5") (pinfunction "A4_5") (pintype "input"))
      (node (ref "IC7") (pin "16") (pinfunction "A1_16") (pintype "input"))
      (node (ref "IC7") (pin "18") (pinfunction "~{RESET}_18") (pintype "input"))
      (node (ref "IC7") (pin "9") (pinfunction "VDD_9") (pintype "power_in"))
      (node (ref "IC8") (pin "2") (pinfunction "A1_2") (pintype "input"))
      (node (ref "IC8") (pin "24") (pinfunction "A5_24") (pintype "input"))
      (node (ref "IC8") (pin "28") (pinfunction "VDD_28") (pintype "power_in"))
      (node (ref "PC1") (pin "+") (pinfunction "+_+") (pintype "passive"))
      (node (ref "PC2") (pin "+") (pinfunction "+_+") (pintype "passive"))
      (node (ref "POT1") (pin "1") (pinfunction "E_1") (pintype "passive"))
      (node (ref "POT1ALT") (pin "1") (pinfunction "E_1") (pintype "passive"))
      (node (ref "POT2") (pin "1") (pinfunction "E_1") (pintype "passive"))
      (node (ref "R33") (pin "2") (pinfunction "2_2") (pintype "passive"))
      (node (ref "SERIAL") (pin "2") (pinfunction "2_2") (pintype "passive"))
      (node (ref "SSW1") (pin "4") (pinfunction "VDD_4") (pintype "bidirectional"))
      (node (ref "U$94") (pin "P$2") (pinfunction "2_P$2") (pintype "passive"))
    )
    (net (code "2") (name "A0") (class "Default")
      (node (ref "POT1") (pin "2A") (pinfunction "S_2A") (pintype "passive"))
      (node (ref "POT1ALT") (pin "2A") (pinfunction "S_2A") (pintype "passive"))
      (node (ref "POT2") (pin "2A") (pinfunction "S_2A") (pintype "passive"))
      (node (ref "SERIAL") (pin "5") (pinfunction "5_5") (pintype "passive"))
    )
    (net (code "3") (name "AD0") (class "Default")
      (node (ref "C12") (pin "1") (pinfunction "1_1") (pintype "passive"))
      (node (ref "IC4") (pin "1") (pinfunction "GPB0_1") (pintype "bidirectional"))
      (node (ref "SW1") (pin "E") (pinfunction "2_E") (pintype "passive"))
    )
    (net (code "4") (name "D2") (class "Default")
      (node (ref "IC4") (pin "21") (pinfunction "GPA0_21") (pintype "bidirectional"))
      (node (ref "IC5") (pin "12") (pinfunction "O_12") (pintype "output"))
    )
    (net (code "5") (name "D3") (class "Default")
      (node (ref "C11") (pin "1") (pinfunction "1_1") (pintype "passive"))
      (node (ref "IC4") (pin "22") (pinfunction "GPA1_22") (pintype "bidirectional"))
      (node (ref "SW1") (pin "A") (pinfunction "A_A") (pintype "passive"))
    )
    (net (code "6") (name "GND") (class "Default")
      (node (ref "B1") (pin "P$4") (pinfunction "SW1_P$4") (pintype "bidirectional"))
      (node (ref "B10") (pin "P$4") (pinfunction "SW1_P$4") (pintype "bidirectional"))
      (node (ref "B10ALT") (pin "P$4") (pinfunction "SW1_P$4") (pintype "bidirectional"))
      (node (ref "B11") (pin "P$4") (pinfunction "SW1_P$4") (pintype "bidirectional"))
      (node (ref "B11ALT") (pin "P$4") (pinfunction "SW1_P$4") (pintype "bidirectional"))
      (node (ref "B12") (pin "P$4") (pinfunction "SW1_P$4") (pintype "bidirectional"))
      (node (ref "B12ALT") (pin "P$4") (pinfunction "SW1_P$4") (pintype "bidirectional"))
      (node (ref "B13") (pin "P$4") (pinfunction "SW1_P$4") (pintype "bidirectional"))
      (node (ref "B13ALT") (pin "P$4") (pinfunction "SW1_P$4") (pintype "bidirectional"))
      (node (ref "B13ALT1") (pin "P$4") (pinfunction "SW1_P$4") (pintype "bidirectional"))
      (node (ref "B14") (pin "P$4") (pinfunction "SW1_P$4") (pintype "bidirectional"))
      (node (ref "B14ALT") (pin "P$4") (pinfunction "SW1_P$4") (pintype "bidirectional"))
      (node (ref "B15") (pin "P$4") (pinfunction "SW1_P$4") (pintype "bidirectional"))
      (node (ref "B15ALT") (pin "P$4") (pinfunction "SW1_P$4") (pintype "bidirectional"))
      (node (ref "B16") (pin "P$4") (pinfunction "SW1_P$4") (pintype "bidirectional"))
      (node (ref "B16ALT") (pin "P$4") (pinfunction "SW1_P$4") (pintype "bidirectional"))
      (node (ref "B17") (pin "P$4") (pinfunction "SW1_P$4") (pintype "bidirectional"))
      (node (ref "B17ALT") (pin "P$4") (pinfunction "SW1_P$4") (pintype "bidirectional"))
      (node (ref "B18") (pin "P$4") (pinfunction "SW1_P$4") (pintype "bidirectional"))
      (node (ref "B18ALT") (pin "P$4") (pinfunction "SW1_P$4") (pintype "bidirectional"))
      (node (ref "B19") (pin "P$4") (pinfunction "SW1_P$4") (pintype "bidirectional"))
      (node (ref "B19ALT") (pin "P$4") (pinfunction "SW1_P$4") (pintype "bidirectional"))
      (node (ref "B1ALT") (pin "P$4") (pinfunction "SW1_P$4") (pintype "bidirectional"))
      (node (ref "B2") (pin "P$4") (pinfunction "SW1_P$4") (pintype "bidirectional"))
      (node (ref "B20") (pin "P$4") (pinfunction "SW1_P$4") (pintype "bidirectional"))
      (node (ref "B20ALT") (pin "P$4") (pinfunction "SW1_P$4") (pintype "bidirectional"))
      (node (ref "B21") (pin "P$4") (pinfunction "SW1_P$4") (pintype "bidirectional"))
      (node (ref "B22") (pin "P$4") (pinfunction "SW1_P$4") (pintype "bidirectional"))
      (node (ref "B23") (pin "P$4") (pinfunction "SW1_P$4") (pintype "bidirectional"))
      (node (ref "B23ALT") (pin "P$4") (pinfunction "SW1_P$4") (pintype "bidirectional"))
      (node (ref "B24") (pin "P$4") (pinfunction "SW1_P$4") (pintype "bidirectional"))
      (node (ref "B24ALT") (pin "P$4") (pinfunction "SW1_P$4") (pintype "bidirectional"))
      (node (ref "B25") (pin "P$4") (pinfunction "SW1_P$4") (pintype "bidirectional"))
      (node (ref "B25ALT") (pin "P$4") (pinfunction "SW1_P$4") (pintype "bidirectional"))
      (node (ref "B26") (pin "P$4") (pinfunction "SW1_P$4") (pintype "bidirectional"))
      (node (ref "B26ALT") (pin "P$4") (pinfunction "SW1_P$4") (pintype "bidirectional"))
      (node (ref "B27") (pin "P$4") (pinfunction "SW1_P$4") (pintype "bidirectional"))
      (node (ref "B27ALT") (pin "P$4") (pinfunction "SW1_P$4") (pintype "bidirectional"))
      (node (ref "B28") (pin "P$4") (pinfunction "SW1_P$4") (pintype "bidirectional"))
      (node (ref "B28ALT") (pin "P$4") (pinfunction "SW1_P$4") (pintype "bidirectional"))
      (node (ref "B29") (pin "P$4") (pinfunction "SW1_P$4") (pintype "bidirectional"))
      (node (ref "B29ALT") (pin "P$4") (pinfunction "SW1_P$4") (pintype "bidirectional"))
      (node (ref "B2ALT") (pin "P$4") (pinfunction "SW1_P$4") (pintype "bidirectional"))
      (node (ref "B3") (pin "P$4") (pinfunction "SW1_P$4") (pintype "bidirectional"))
      (node (ref "B30") (pin "P$4") (pinfunction "SW1_P$4") (pintype "bidirectional"))
      (node (ref "B30ALT") (pin "P$4") (pinfunction "SW1_P$4") (pintype "bidirectional"))
      (node (ref "B31") (pin "P$4") (pinfunction "SW1_P$4") (pintype "bidirectional"))
      (node (ref "B31ALT") (pin "P$4") (pinfunction "SW1_P$4") (pintype "bidirectional"))
      (node (ref "B32") (pin "P$4") (pinfunction "SW1_P$4") (pintype "bidirectional"))
      (node (ref "B32ALT") (pin "P$4") (pinfunction "SW1_P$4") (pintype "bidirectional"))
      (node (ref "B3ALT") (pin "P$4") (pinfunction "SW1_P$4") (pintype "bidirectional"))
      (node (ref "B4") (pin "P$4") (pinfunction "SW1_P$4") (pintype "bidirectional"))
      (node (ref "B4ALT") (pin "P$4") (pinfunction "SW1_P$4") (pintype "bidirectional"))
      (node (ref "B5") (pin "P$4") (pinfunction "SW1_P$4") (pintype "bidirectional"))
      (node (ref "B5ALT") (pin "P$4") (pinfunction "SW1_P$4") (pintype "bidirectional"))
      (node (ref "B5ALT1") (pin "P$4") (pinfunction "SW1_P$4") (pintype "bidirectional"))
      (node (ref "B6") (pin "P$4") (pinfunction "SW1_P$4") (pintype "bidirectional"))
      (node (ref "B6ALT") (pin "P$4") (pinfunction "SW1_P$4") (pintype "bidirectional"))
      (node (ref "B6ALT1") (pin "P$4") (pinfunction "SW1_P$4") (pintype "bidirectional"))
      (node (ref "B7") (pin "P$4") (pinfunction "SW1_P$4") (pintype "bidirectional"))
      (node (ref "B7ALT") (pin "P$4") (pinfunction "SW1_P$4") (pintype "bidirectional"))
      (node (ref "B7ALT1") (pin "P$4") (pinfunction "SW1_P$4") (pintype "bidirectional"))
      (node (ref "B8") (pin "P$4") (pinfunction "SW1_P$4") (pintype "bidirectional"))
      (node (ref "B8ALT") (pin "P$4") (pinfunction "SW1_P$4") (pintype "bidirectional"))
      (node (ref "B9") (pin "P$4") (pinfunction "SW1_P$4") (pintype "bidirectional"))
      (node (ref "B9ALT") (pin "P$4") (pinfunction "SW1_P$4") (pintype "bidirectional"))
      (node (ref "B9ALT2") (pin "P$4") (pinfunction "SW1_P$4") (pintype "bidirectional"))
      (node (ref "C1") (pin "1") (pinfunction "1_1") (pintype "passive"))
      (node (ref "C10") (pin "2") (pinfunction "2_2") (pintype "passive"))
      (node (ref "C11") (pin "2") (pinfunction "2_2") (pintype "passive"))
      (node (ref "C12") (pin "2") (pinfunction "2_2") (pintype "passive"))
      (node (ref "C13") (pin "1") (pinfunction "1_1") (pintype "passive"))
      (node (ref "C14") (pin "2") (pinfunction "2_2") (pintype "passive"))
      (node (ref "C15") (pin "2") (pinfunction "2_2") (pintype "passive"))
      (node (ref "C16") (pin "2") (pinfunction "2_2") (pintype "passive"))
      (node (ref "C17") (pin "2") (pinfunction "2_2") (pintype "passive"))
      (node (ref "C18") (pin "2") (pinfunction "2_2") (pintype "passive"))
      (node (ref "C19") (pin "2") (pinfunction "2_2") (pintype "passive"))
      (node (ref "C2") (pin "2") (pinfunction "2_2") (pintype "passive"))
      (node (ref "C22") (pin "2") (pinfunction "2_2") (pintype "passive"))
      (node (ref "C3") (pin "1") (pinfunction "1_1") (pintype "passive"))
      (node (ref "C4") (pin "2") (pinfunction "2_2") (pintype "passive"))
      (node (ref "C5") (pin "2") (pinfunction "2_2") (pintype "passive"))
      (node (ref "C6") (pin "2") (pinfunction "2_2") (pintype "passive"))
      (node (ref "C7") (pin "2") (pinfunction "2_2") (pintype "passive"))
      (node (ref "C8") (pin "2") (pinfunction "2_2") (pintype "passive"))
      (node (ref "C9") (pin "1") (pinfunction "1_1") (pintype "passive"))
      (node (ref "IC1") (pin "10") (pinfunction "VSS_10") (pintype "power_in"))
      (node (ref "IC1") (pin "16") (pinfunction "A1_16") (pintype "input"))
      (node (ref "IC1") (pin "17") (pinfunction "A2_17") (pintype "input"))
      (node (ref "IC2") (pin "14") (pinfunction "GND_14") (pintype "power_in"))
      (node (ref "IC2") (pin "2") (pinfunction "A1_2") (pintype "input"))
      (node (ref "IC2") (pin "23") (pinfunction "OE_23") (pintype "input"))
      (node (ref "IC2") (pin "25") (pinfunction "EXTCLK_25") (pintype "input"))
      (node (ref "IC2") (pin "3") (pinfunction "A2_3") (pintype "input"))
      (node (ref "IC3") (pin "14") (pinfunction "GND_14") (pintype "power_in"))
      (node (ref "IC3") (pin "2") (pinfunction "A1_2") (pintype "input"))
      (node (ref "IC3") (pin "23") (pinfunction "OE_23") (pintype "input"))
      (node (ref "IC3") (pin "25") (pinfunction "EXTCLK_25") (pintype "input"))
      (node (ref "IC3") (pin "3") (pinfunction "A2_3") (pintype "input"))
      (node (ref "IC3") (pin "4") (pinfunction "A3_4") (pintype "input"))
      (node (ref "IC3") (pin "5") (pinfunction "A4_5") (pintype "input"))
      (node (ref "IC4") (pin "10") (pinfunction "VSS_10") (pintype "power_in"))
      (node (ref "IC4") (pin "15") (pinfunction "A0_15") (pintype "input"))
      (node (ref "IC4") (pin "16") (pinfunction "A1_16") (pintype "input"))
      (node (ref "IC4") (pin "17") (pinfunction "A2_17") (pintype "input"))
      (node (ref "IC5") (pin "1") (pinfunction "I_1") (pintype "input"))
      (node (ref "IC5") (pin "11") (pinfunction "I_11") (pintype "input"))
      (node (ref "IC5") (pin "3") (pinfunction "I_3") (pintype "input"))
      (node (ref "IC5") (pin "5") (pinfunction "I_5") (pintype "input"))
      (node (ref "IC5") (pin "7") (pinfunction "GND_7") (pintype "power_in"))
      (node (ref "IC5") (pin "9") (pinfunction "I_9") (pintype "input"))
      (node (ref "IC6") (pin "1") (pinfunction "A0_1") (pintype "input"))
      (node (ref "IC6") (pin "14") (pinfunction "GND_14") (pintype "power_in"))
      (node (ref "IC6") (pin "23") (pinfunction "OE_23") (pintype "input"))
      (node (ref "IC6") (pin "25") (pinfunction "EXTCLK_25") (pintype "input"))
      (node (ref "IC6") (pin "3") (pinfunction "A2_3") (pintype "input"))
      (node (ref "IC7") (pin "10") (pinfunction "VSS_10") (pintype "power_in"))
      (node (ref "IC7") (pin "15") (pinfunction "A0_15") (pintype "input"))
      (node (ref "IC7") (pin "17") (pinfunction "A2_17") (pintype "input"))
      (node (ref "IC8") (pin "1") (pinfunction "A0_1") (pintype "input"))
      (node (ref "IC8") (pin "14") (pinfunction "GND_14") (pintype "power_in"))
      (node (ref "IC8") (pin "23") (pinfunction "OE_23") (pintype "input"))
      (node (ref "IC8") (pin "25") (pinfunction "EXTCLK_25") (pintype "input"))
      (node (ref "IC8") (pin "3") (pinfunction "A2_3") (pintype "input"))
      (node (ref "IC8") (pin "4") (pinfunction "A3_4") (pintype "input"))
      (node (ref "IC8") (pin "5") (pinfunction "A4_5") (pintype "input"))
      (node (ref "PC1") (pin "-") (pinfunction "-_-") (pintype "passive"))
      (node (ref "PC2") (pin "-") (pinfunction "-_-") (pintype "passive"))
      (node (ref "POT1") (pin "3") (pinfunction "A_3") (pintype "passive"))
      (node (ref "POT1ALT") (pin "3") (pinfunction "A_3") (pintype "passive"))
      (node (ref "POT2") (pin "3") (pinfunction "A_3") (pintype "passive"))
      (node (ref "SERIAL") (pin "1") (pinfunction "1_1") (pintype "passive"))
      (node (ref "SSW1") (pin "1") (pinfunction "SW1_1") (pintype "bidirectional"))
      (node (ref "SSW1") (pin "3") (pinfunction "GND_3") (pintype "bidirectional"))
      (node (ref "SW1") (pin "C") (pinfunction "C_C") (pintype "passive"))
      (node (ref "SW1") (pin "D") (pinfunction "1_D") (pintype "passive"))
      (node (ref "U$25") (pin "P$1") (pinfunction "1_P$1") (pintype "passive"))
      (node (ref "U$26") (pin "P$1") (pinfunction "1_P$1") (pintype "passive"))
      (node (ref "U$27") (pin "P$1") (pinfunction "1_P$1") (pintype "passive"))
      (node (ref "U$28") (pin "P$1") (pinfunction "1_P$1") (pintype "passive"))
      (node (ref "U$51") (pin "P$1") (pinfunction "1_P$1") (pintype "passive"))
      (node (ref "U$94") (pin "P$1") (pinfunction "1_P$1") (pintype "passive"))
    )
    (net (code "7") (name "GPA0") (class "Default")
      (node (ref "B8") (pin "P$5") (pinfunction "SW2_P$5") (pintype "bidirectional"))
      (node (ref "B8ALT") (pin "P$5") (pinfunction "SW2_P$5") (pintype "bidirectional"))
      (node (ref "IC1") (pin "21") (pinfunction "GPA0_21") (pintype "bidirectional"))
    )
    (net (code "8") (name "GPA1") (class "Default")
      (node (ref "B7") (pin "P$5") (pinfunction "SW2_P$5") (pintype "bidirectional"))
      (node (ref "B7ALT") (pin "P$5") (pinfunction "SW2_P$5") (pintype "bidirectional"))
      (node (ref "B7ALT1") (pin "P$5") (pinfunction "SW2_P$5") (pintype "bidirectional"))
      (node (ref "IC1") (pin "22") (pinfunction "GPA1_22") (pintype "bidirectional"))
    )
    (net (code "9") (name "GPA2") (class "Default")
      (node (ref "B6") (pin "P$5") (pinfunction "SW2_P$5") (pintype "bidirectional"))
      (node (ref "B6ALT") (pin "P$5") (pinfunction "SW2_P$5") (pintype "bidirectional"))
      (node (ref "B6ALT1") (pin "P$5") (pinfunction "SW2_P$5") (pintype "bidirectional"))
      (node (ref "IC1") (pin "23") (pinfunction "GPA2_23") (pintype "bidirectional"))
    )
    (net (code "10") (name "GPA3") (class "Default")
      (node (ref "B5") (pin "P$5") (pinfunction "SW2_P$5") (pintype "bidirectional"))
      (node (ref "B5ALT") (pin "P$5") (pinfunction "SW2_P$5") (pintype "bidirectional"))
      (node (ref "B5ALT1") (pin "P$5") (pinfunction "SW2_P$5") (pintype "bidirectional"))
      (node (ref "IC1") (pin "24") (pinfunction "GPA3_24") (pintype "bidirectional"))
    )
    (net (code "11") (name "GPA4") (class "Default")
      (node (ref "B1") (pin "P$5") (pinfunction "SW2_P$5") (pintype "bidirectional"))
      (node (ref "B1ALT") (pin "P$5") (pinfunction "SW2_P$5") (pintype "bidirectional"))
      (node (ref "IC1") (pin "25") (pinfunction "GPA4_25") (pintype "bidirectional"))
    )
    (net (code "12") (name "GPA4S") (class "Default")
      (node (ref "IC4") (pin "25") (pinfunction "GPA4_25") (pintype "bidirectional"))
      (node (ref "SSW1") (pin "2") (pinfunction "SW2_2") (pintype "bidirectional"))
    )
    (net (code "13") (name "GPA5") (class "Default")
      (node (ref "B2") (pin "P$5") (pinfunction "SW2_P$5") (pintype "bidirectional"))
      (node (ref "B2ALT") (pin "P$5") (pinfunction "SW2_P$5") (pintype "bidirectional"))
      (node (ref "IC1") (pin "26") (pinfunction "GPA5_26") (pintype "bidirectional"))
    )
    (net (code "14") (name "GPA6") (class "Default")
      (node (ref "B3") (pin "P$5") (pinfunction "SW2_P$5") (pintype "bidirectional"))
      (node (ref "B3ALT") (pin "P$5") (pinfunction "SW2_P$5") (pintype "bidirectional"))
      (node (ref "IC1") (pin "27") (pinfunction "GPA6_27") (pintype "bidirectional"))
    )
    (net (code "15") (name "GPA7") (class "Default")
      (node (ref "B4") (pin "P$5") (pinfunction "SW2_P$5") (pintype "bidirectional"))
      (node (ref "B4ALT") (pin "P$5") (pinfunction "SW2_P$5") (pintype "bidirectional"))
      (node (ref "IC1") (pin "28") (pinfunction "GPA7_28") (pintype "bidirectional"))
    )
    (net (code "16") (name "GPA8") (class "Default")
      (node (ref "B16") (pin "P$5") (pinfunction "SW2_P$5") (pintype "bidirectional"))
      (node (ref "B16ALT") (pin "P$5") (pinfunction "SW2_P$5") (pintype "bidirectional"))
      (node (ref "IC1") (pin "1") (pinfunction "GPB0_1") (pintype "bidirectional"))
    )
    (net (code "17") (name "GPA9") (class "Default")
      (node (ref "B15") (pin "P$5") (pinfunction "SW2_P$5") (pintype "bidirectional"))
      (node (ref "B15ALT") (pin "P$5") (pinfunction "SW2_P$5") (pintype "bidirectional"))
      (node (ref "IC1") (pin "2") (pinfunction "GPB1_2") (pintype "bidirectional"))
    )
    (net (code "18") (name "GPA10") (class "Default")
      (node (ref "B14") (pin "P$5") (pinfunction "SW2_P$5") (pintype "bidirectional"))
      (node (ref "B14ALT") (pin "P$5") (pinfunction "SW2_P$5") (pintype "bidirectional"))
      (node (ref "IC1") (pin "3") (pinfunction "GPB2_3") (pintype "bidirectional"))
    )
    (net (code "19") (name "GPA11") (class "Default")
      (node (ref "B13") (pin "P$5") (pinfunction "SW2_P$5") (pintype "bidirectional"))
      (node (ref "B13ALT") (pin "P$5") (pinfunction "SW2_P$5") (pintype "bidirectional"))
      (node (ref "B13ALT1") (pin "P$5") (pinfunction "SW2_P$5") (pintype "bidirectional"))
      (node (ref "IC1") (pin "4") (pinfunction "GPB3_4") (pintype "bidirectional"))
    )
    (net (code "20") (name "GPA12") (class "Default")
      (node (ref "B9") (pin "P$5") (pinfunction "SW2_P$5") (pintype "bidirectional"))
      (node (ref "B9ALT") (pin "P$5") (pinfunction "SW2_P$5") (pintype "bidirectional"))
      (node (ref "B9ALT2") (pin "P$5") (pinfunction "SW2_P$5") (pintype "bidirectional"))
      (node (ref "IC1") (pin "5") (pinfunction "GPB4_5") (pintype "bidirectional"))
    )
    (net (code "21") (name "GPA13") (class "Default")
      (node (ref "B10") (pin "P$5") (pinfunction "SW2_P$5") (pintype "bidirectional"))
      (node (ref "B10ALT") (pin "P$5") (pinfunction "SW2_P$5") (pintype "bidirectional"))
      (node (ref "IC1") (pin "6") (pinfunction "GPB5_6") (pintype "bidirectional"))
    )
    (net (code "22") (name "GPA14") (class "Default")
      (node (ref "B11") (pin "P$5") (pinfunction "SW2_P$5") (pintype "bidirectional"))
      (node (ref "B11ALT") (pin "P$5") (pinfunction "SW2_P$5") (pintype "bidirectional"))
      (node (ref "IC1") (pin "7") (pinfunction "GPB6_7") (pintype "bidirectional"))
    )
    (net (code "23") (name "GPA15") (class "Default")
      (node (ref "B12") (pin "P$5") (pinfunction "SW2_P$5") (pintype "bidirectional"))
      (node (ref "B12ALT") (pin "P$5") (pinfunction "SW2_P$5") (pintype "bidirectional"))
      (node (ref "IC1") (pin "8") (pinfunction "GPB7_8") (pintype "bidirectional"))
    )
    (net (code "24") (name "GPA16") (class "Default")
      (node (ref "B24") (pin "P$5") (pinfunction "SW2_P$5") (pintype "bidirectional"))
      (node (ref "B24ALT") (pin "P$5") (pinfunction "SW2_P$5") (pintype "bidirectional"))
      (node (ref "IC7") (pin "21") (pinfunction "GPA0_21") (pintype "bidirectional"))
    )
    (net (code "25") (name "GPA17") (class "Default")
      (node (ref "B23") (pin "P$5") (pinfunction "SW2_P$5") (pintype "bidirectional"))
      (node (ref "B23ALT") (pin "P$5") (pinfunction "SW2_P$5") (pintype "bidirectional"))
      (node (ref "IC7") (pin "22") (pinfunction "GPA1_22") (pintype "bidirectional"))
    )
    (net (code "26") (name "GPA18") (class "Default")
      (node (ref "B22") (pin "P$5") (pinfunction "SW2_P$5") (pintype "bidirectional"))
      (node (ref "IC7") (pin "23") (pinfunction "GPA2_23") (pintype "bidirectional"))
    )
    (net (code "27") (name "GPA19") (class "Default")
      (node (ref "B21") (pin "P$5") (pinfunction "SW2_P$5") (pintype "bidirectional"))
      (node (ref "IC7") (pin "24") (pinfunction "GPA3_24") (pintype "bidirectional"))
    )
    (net (code "28") (name "GPA20") (class "Default")
      (node (ref "B17") (pin "P$5") (pinfunction "SW2_P$5") (pintype "bidirectional"))
      (node (ref "B17ALT") (pin "P$5") (pinfunction "SW2_P$5") (pintype "bidirectional"))
      (node (ref "IC7") (pin "25") (pinfunction "GPA4_25") (pintype "bidirectional"))
    )
    (net (code "29") (name "GPA21") (class "Default")
      (node (ref "B18") (pin "P$5") (pinfunction "SW2_P$5") (pintype "bidirectional"))
      (node (ref "B18ALT") (pin "P$5") (pinfunction "SW2_P$5") (pintype "bidirectional"))
      (node (ref "IC7") (pin "26") (pinfunction "GPA5_26") (pintype "bidirectional"))
    )
    (net (code "30") (name "GPA22") (class "Default")
      (node (ref "B19") (pin "P$5") (pinfunction "SW2_P$5") (pintype "bidirectional"))
      (node (ref "B19ALT") (pin "P$5") (pinfunction "SW2_P$5") (pintype "bidirectional"))
      (node (ref "IC7") (pin "27") (pinfunction "GPA6_27") (pintype "bidirectional"))
    )
    (net (code "31") (name "GPA23") (class "Default")
      (node (ref "B20") (pin "P$5") (pinfunction "SW2_P$5") (pintype "bidirectional"))
      (node (ref "B20ALT") (pin "P$5") (pinfunction "SW2_P$5") (pintype "bidirectional"))
      (node (ref "IC7") (pin "28") (pinfunction "GPA7_28") (pintype "bidirectional"))
    )
    (net (code "32") (name "GPA24") (class "Default")
      (node (ref "B32") (pin "P$5") (pinfunction "SW2_P$5") (pintype "bidirectional"))
      (node (ref "B32ALT") (pin "P$5") (pinfunction "SW2_P$5") (pintype "bidirectional"))
      (node (ref "IC7") (pin "1") (pinfunction "GPB0_1") (pintype "bidirectional"))
    )
    (net (code "33") (name "GPA25") (class "Default")
      (node (ref "B31") (pin "P$5") (pinfunction "SW2_P$5") (pintype "bidirectional"))
      (node (ref "B31ALT") (pin "P$5") (pinfunction "SW2_P$5") (pintype "bidirectional"))
      (node (ref "IC7") (pin "2") (pinfunction "GPB1_2") (pintype "bidirectional"))
    )
    (net (code "34") (name "GPA26") (class "Default")
      (node (ref "B30") (pin "P$5") (pinfunction "SW2_P$5") (pintype "bidirectional"))
      (node (ref "B30ALT") (pin "P$5") (pinfunction "SW2_P$5") (pintype "bidirectional"))
      (node (ref "IC7") (pin "3") (pinfunction "GPB2_3") (pintype "bidirectional"))
    )
    (net (code "35") (name "GPA27") (class "Default")
      (node (ref "B29") (pin "P$5") (pinfunction "SW2_P$5") (pintype "bidirectional"))
      (node (ref "B29ALT") (pin "P$5") (pinfunction "SW2_P$5") (pintype "bidirectional"))
      (node (ref "IC7") (pin "4") (pinfunction "GPB3_4") (pintype "bidirectional"))
    )
    (net (code "36") (name "GPA28") (class "Default")
      (node (ref "B25") (pin "P$5") (pinfunction "SW2_P$5") (pintype "bidirectional"))
      (node (ref "B25ALT") (pin "P$5") (pinfunction "SW2_P$5") (pintype "bidirectional"))
      (node (ref "IC7") (pin "5") (pinfunction "GPB4_5") (pintype "bidirectional"))
    )
    (net (code "37") (name "GPA29") (class "Default")
      (node (ref "B26") (pin "P$5") (pinfunction "SW2_P$5") (pintype "bidirectional"))
      (node (ref "B26ALT") (pin "P$5") (pinfunction "SW2_P$5") (pintype "bidirectional"))
      (node (ref "IC7") (pin "6") (pinfunction "GPB5_6") (pintype "bidirectional"))
    )
    (net (code "38") (name "GPA30") (class "Default")
      (node (ref "B27") (pin "P$5") (pinfunction "SW2_P$5") (pintype "bidirectional"))
      (node (ref "B27ALT") (pin "P$5") (pinfunction "SW2_P$5") (pintype "bidirectional"))
      (node (ref "IC7") (pin "7") (pinfunction "GPB6_7") (pintype "bidirectional"))
    )
    (net (code "39") (name "GPA31") (class "Default")
      (node (ref "B28") (pin "P$5") (pinfunction "SW2_P$5") (pintype "bidirectional"))
      (node (ref "B28ALT") (pin "P$5") (pinfunction "SW2_P$5") (pintype "bidirectional"))
      (node (ref "IC7") (pin "8") (pinfunction "GPB7_8") (pintype "bidirectional"))
    )
    (net (code "40") (name "GPB4") (class "Default")
      (node (ref "IC4") (pin "5") (pinfunction "GPB4_5") (pintype "bidirectional"))
      (node (ref "SSW1") (pin "8") (pinfunction "SS_8") (pintype "bidirectional"))
    )
    (net (code "41") (name "I2C_SCL") (class "Default")
      (node (ref "IC1") (pin "12") (pinfunction "SCL_12") (pintype "input"))
      (node (ref "IC2") (pin "26") (pinfunction "SCL_26") (pintype "input"))
      (node (ref "IC3") (pin "26") (pinfunction "SCL_26") (pintype "input"))
      (node (ref "IC4") (pin "12") (pinfunction "SCL_12") (pintype "input"))
      (node (ref "IC6") (pin "26") (pinfunction "SCL_26") (pintype "input"))
      (node (ref "IC7") (pin "12") (pinfunction "SCL_12") (pintype "input"))
      (node (ref "IC8") (pin "26") (pinfunction "SCL_26") (pintype "input"))
      (node (ref "SERIAL") (pin "4") (pinfunction "4_4") (pintype "passive"))
      (node (ref "U$94") (pin "P$4") (pinfunction "4_P$4") (pintype "passive"))
    )
    (net (code "42") (name "I2C_SDA") (class "Default")
      (node (ref "IC1") (pin "13") (pinfunction "SDA_13") (pintype "bidirectional"))
      (node (ref "IC2") (pin "27") (pinfunction "SDA_27") (pintype "input"))
      (node (ref "IC3") (pin "27") (pinfunction "SDA_27") (pintype "input"))
      (node (ref "IC4") (pin "13") (pinfunction "SDA_13") (pintype "bidirectional"))
      (node (ref "IC6") (pin "27") (pinfunction "SDA_27") (pintype "input"))
      (node (ref "IC7") (pin "13") (pinfunction "SDA_13") (pintype "bidirectional"))
      (node (ref "IC8") (pin "27") (pinfunction "SDA_27") (pintype "input"))
      (node (ref "SERIAL") (pin "3") (pinfunction "3_3") (pintype "passive"))
      (node (ref "U$94") (pin "P$3") (pinfunction "3_P$3") (pintype "passive"))
    )
    (net (code "43") (name "L0") (class "Default")
      (node (ref "B1") (pin "P$2") (pinfunction "K1_P$2") (pintype "bidirectional"))
      (node (ref "B1ALT") (pin "P$2") (pinfunction "K1_P$2") (pintype "bidirectional"))
      (node (ref "R20") (pin "1") (pinfunction "1_1") (pintype "passive"))
    )
    (net (code "44") (name "L1") (class "Default")
      (node (ref "B1") (pin "P$3") (pinfunction "K2_P$3") (pintype "bidirectional"))
      (node (ref "B1ALT") (pin "P$3") (pinfunction "K2_P$3") (pintype "bidirectional"))
      (node (ref "R19") (pin "1") (pinfunction "1_1") (pintype "passive"))
    )
    (net (code "45") (name "L2") (class "Default")
      (node (ref "B2") (pin "P$2") (pinfunction "K1_P$2") (pintype "bidirectional"))
      (node (ref "B2ALT") (pin "P$2") (pinfunction "K1_P$2") (pintype "bidirectional"))
      (node (ref "R18") (pin "1") (pinfunction "1_1") (pintype "passive"))
    )
    (net (code "46") (name "L3") (class "Default")
      (node (ref "B2") (pin "P$3") (pinfunction "K2_P$3") (pintype "bidirectional"))
      (node (ref "B2ALT") (pin "P$3") (pinfunction "K2_P$3") (pintype "bidirectional"))
      (node (ref "R17") (pin "1") (pinfunction "1_1") (pintype "passive"))
    )
    (net (code "47") (name "L4") (class "Default")
      (node (ref "B3") (pin "P$2") (pinfunction "K1_P$2") (pintype "bidirectional"))
      (node (ref "B3ALT") (pin "P$2") (pinfunction "K1_P$2") (pintype "bidirectional"))
      (node (ref "R16") (pin "1") (pinfunction "1_1") (pintype "passive"))
    )
    (net (code "48") (name "L5") (class "Default")
      (node (ref "B3") (pin "P$3") (pinfunction "K2_P$3") (pintype "bidirectional"))
      (node (ref "B3ALT") (pin "P$3") (pinfunction "K2_P$3") (pintype "bidirectional"))
      (node (ref "R15") (pin "1") (pinfunction "1_1") (pintype "passive"))
    )
    (net (code "49") (name "L6") (class "Default")
      (node (ref "B4") (pin "P$2") (pinfunction "K1_P$2") (pintype "bidirectional"))
      (node (ref "B4ALT") (pin "P$2") (pinfunction "K1_P$2") (pintype "bidirectional"))
      (node (ref "R14") (pin "1") (pinfunction "1_1") (pintype "passive"))
    )
    (net (code "50") (name "L7") (class "Default")
      (node (ref "B4") (pin "P$3") (pinfunction "K2_P$3") (pintype "bidirectional"))
      (node (ref "B4ALT") (pin "P$3") (pinfunction "K2_P$3") (pintype "bidirectional"))
      (node (ref "R13") (pin "1") (pinfunction "1_1") (pintype "passive"))
    )
    (net (code "51") (name "L8") (class "Default")
      (node (ref "B5") (pin "P$2") (pinfunction "K1_P$2") (pintype "bidirectional"))
      (node (ref "B5ALT") (pin "P$2") (pinfunction "K1_P$2") (pintype "bidirectional"))
      (node (ref "B5ALT1") (pin "P$2") (pinfunction "K1_P$2") (pintype "bidirectional"))
      (node (ref "R12") (pin "1") (pinfunction "1_1") (pintype "passive"))
    )
    (net (code "52") (name "L9") (class "Default")
      (node (ref "B5") (pin "P$3") (pinfunction "K2_P$3") (pintype "bidirectional"))
      (node (ref "B5ALT") (pin "P$3") (pinfunction "K2_P$3") (pintype "bidirectional"))
      (node (ref "B5ALT1") (pin "P$3") (pinfunction "K2_P$3") (pintype "bidirectional"))
      (node (ref "R11") (pin "1") (pinfunction "1_1") (pintype "passive"))
    )
    (net (code "53") (name "L10") (class "Default")
      (node (ref "B6") (pin "P$2") (pinfunction "K1_P$2") (pintype "bidirectional"))
      (node (ref "B6ALT") (pin "P$2") (pinfunction "K1_P$2") (pintype "bidirectional"))
      (node (ref "B6ALT1") (pin "P$2") (pinfunction "K1_P$2") (pintype "bidirectional"))
      (node (ref "R10") (pin "1") (pinfunction "1_1") (pintype "passive"))
    )
    (net (code "54") (name "L11") (class "Default")
      (node (ref "B6") (pin "P$3") (pinfunction "K2_P$3") (pintype "bidirectional"))
      (node (ref "B6ALT") (pin "P$3") (pinfunction "K2_P$3") (pintype "bidirectional"))
      (node (ref "B6ALT1") (pin "P$3") (pinfunction "K2_P$3") (pintype "bidirectional"))
      (node (ref "R9") (pin "1") (pinfunction "1_1") (pintype "passive"))
    )
    (net (code "55") (name "L12") (class "Default")
      (node (ref "B7") (pin "P$2") (pinfunction "K1_P$2") (pintype "bidirectional"))
      (node (ref "B7ALT") (pin "P$2") (pinfunction "K1_P$2") (pintype "bidirectional"))
      (node (ref "B7ALT1") (pin "P$2") (pinfunction "K1_P$2") (pintype "bidirectional"))
      (node (ref "R8") (pin "1") (pinfunction "1_1") (pintype "passive"))
    )
    (net (code "56") (name "L13") (class "Default")
      (node (ref "B7") (pin "P$3") (pinfunction "K2_P$3") (pintype "bidirectional"))
      (node (ref "B7ALT") (pin "P$3") (pinfunction "K2_P$3") (pintype "bidirectional"))
      (node (ref "B7ALT1") (pin "P$3") (pinfunction "K2_P$3") (pintype "bidirectional"))
      (node (ref "R7") (pin "1") (pinfunction "1_1") (pintype "passive"))
    )
    (net (code "57") (name "L14") (class "Default")
      (node (ref "B8") (pin "P$2") (pinfunction "K1_P$2") (pintype "bidirectional"))
      (node (ref "B8ALT") (pin "P$2") (pinfunction "K1_P$2") (pintype "bidirectional"))
      (node (ref "R6") (pin "1") (pinfunction "1_1") (pintype "passive"))
    )
    (net (code "58") (name "L15") (class "Default")
      (node (ref "B8") (pin "P$3") (pinfunction "K2_P$3") (pintype "bidirectional"))
      (node (ref "B8ALT") (pin "P$3") (pinfunction "K2_P$3") (pintype "bidirectional"))
      (node (ref "R5") (pin "1") (pinfunction "1_1") (pintype "passive"))
    )
    (net (code "59") (name "L16") (class "Default")
      (node (ref "B9") (pin "P$2") (pinfunction "K1_P$2") (pintype "bidirectional"))
      (node (ref "B9ALT") (pin "P$2") (pinfunction "K1_P$2") (pintype "bidirectional"))
      (node (ref "B9ALT2") (pin "P$2") (pinfunction "K1_P$2") (pintype "bidirectional"))
      (node (ref "R32") (pin "1") (pinfunction "1_1") (pintype "passive"))
    )
    (net (code "60") (name "L17") (class "Default")
      (node (ref "B9") (pin "P$3") (pinfunction "K2_P$3") (pintype "bidirectional"))
      (node (ref "B9ALT") (pin "P$3") (pinfunction "K2_P$3") (pintype "bidirectional"))
      (node (ref "B9ALT2") (pin "P$3") (pinfunction "K2_P$3") (pintype "bidirectional"))
      (node (ref "R31") (pin "1") (pinfunction "1_1") (pintype "passive"))
    )
    (net (code "61") (name "L18") (class "Default")
      (node (ref "B10") (pin "P$2") (pinfunction "K1_P$2") (pintype "bidirectional"))
      (node (ref "B10ALT") (pin "P$2") (pinfunction "K1_P$2") (pintype "bidirectional"))
      (node (ref "R30") (pin "1") (pinfunction "1_1") (pintype "passive"))
    )
    (net (code "62") (name "L19") (class "Default")
      (node (ref "B10") (pin "P$3") (pinfunction "K2_P$3") (pintype "bidirectional"))
      (node (ref "B10ALT") (pin "P$3") (pinfunction "K2_P$3") (pintype "bidirectional"))
      (node (ref "R29") (pin "1") (pinfunction "1_1") (pintype "passive"))
    )
    (net (code "63") (name "L20") (class "Default")
      (node (ref "B11") (pin "P$2") (pinfunction "K1_P$2") (pintype "bidirectional"))
      (node (ref "B11ALT") (pin "P$2") (pinfunction "K1_P$2") (pintype "bidirectional"))
      (node (ref "R28") (pin "1") (pinfunction "1_1") (pintype "passive"))
    )
    (net (code "64") (name "L21") (class "Default")
      (node (ref "B11") (pin "P$3") (pinfunction "K2_P$3") (pintype "bidirectional"))
      (node (ref "B11ALT") (pin "P$3") (pinfunction "K2_P$3") (pintype "bidirectional"))
      (node (ref "R27") (pin "1") (pinfunction "1_1") (pintype "passive"))
    )
    (net (code "65") (name "L22") (class "Default")
      (node (ref "B12") (pin "P$2") (pinfunction "K1_P$2") (pintype "bidirectional"))
      (node (ref "B12ALT") (pin "P$2") (pinfunction "K1_P$2") (pintype "bidirectional"))
      (node (ref "R57") (pin "1") (pinfunction "1_1") (pintype "passive"))
    )
    (net (code "66") (name "L23") (class "Default")
      (node (ref "B12") (pin "P$3") (pinfunction "K2_P$3") (pintype "bidirectional"))
      (node (ref "B12ALT") (pin "P$3") (pinfunction "K2_P$3") (pintype "bidirectional"))
      (node (ref "R56") (pin "1") (pinfunction "1_1") (pintype "passive"))
    )
    (net (code "67") (name "L24") (class "Default")
      (node (ref "B13") (pin "P$2") (pinfunction "K1_P$2") (pintype "bidirectional"))
      (node (ref "B13ALT") (pin "P$2") (pinfunction "K1_P$2") (pintype "bidirectional"))
      (node (ref "B13ALT1") (pin "P$2") (pinfunction "K1_P$2") (pintype "bidirectional"))
      (node (ref "R63") (pin "1") (pinfunction "1_1") (pintype "passive"))
    )
    (net (code "68") (name "L25") (class "Default")
      (node (ref "B13") (pin "P$3") (pinfunction "K2_P$3") (pintype "bidirectional"))
      (node (ref "B13ALT") (pin "P$3") (pinfunction "K2_P$3") (pintype "bidirectional"))
      (node (ref "B13ALT1") (pin "P$3") (pinfunction "K2_P$3") (pintype "bidirectional"))
      (node (ref "R62") (pin "1") (pinfunction "1_1") (pintype "passive"))
    )
    (net (code "69") (name "L26") (class "Default")
      (node (ref "B14") (pin "P$2") (pinfunction "K1_P$2") (pintype "bidirectional"))
      (node (ref "B14ALT") (pin "P$2") (pinfunction "K1_P$2") (pintype "bidirectional"))
      (node (ref "R61") (pin "1") (pinfunction "1_1") (pintype "passive"))
    )
    (net (code "70") (name "L27") (class "Default")
      (node (ref "B14") (pin "P$3") (pinfunction "K2_P$3") (pintype "bidirectional"))
      (node (ref "B14ALT") (pin "P$3") (pinfunction "K2_P$3") (pintype "bidirectional"))
      (node (ref "R60") (pin "1") (pinfunction "1_1") (pintype "passive"))
    )
    (net (code "71") (name "L28") (class "Default")
      (node (ref "B15") (pin "P$2") (pinfunction "K1_P$2") (pintype "bidirectional"))
      (node (ref "B15ALT") (pin "P$2") (pinfunction "K1_P$2") (pintype "bidirectional"))
      (node (ref "R59") (pin "1") (pinfunction "1_1") (pintype "passive"))
    )
    (net (code "72") (name "L29") (class "Default")
      (node (ref "B15") (pin "P$3") (pinfunction "K2_P$3") (pintype "bidirectional"))
      (node (ref "B15ALT") (pin "P$3") (pinfunction "K2_P$3") (pintype "bidirectional"))
      (node (ref "R58") (pin "1") (pinfunction "1_1") (pintype "passive"))
    )
    (net (code "73") (name "L30") (class "Default")
      (node (ref "B16") (pin "P$2") (pinfunction "K1_P$2") (pintype "bidirectional"))
      (node (ref "B16ALT") (pin "P$2") (pinfunction "K1_P$2") (pintype "bidirectional"))
      (node (ref "R65") (pin "1") (pinfunction "1_1") (pintype "passive"))
    )
    (net (code "74") (name "L31") (class "Default")
      (node (ref "B16") (pin "P$3") (pinfunction "K2_P$3") (pintype "bidirectional"))
      (node (ref "B16ALT") (pin "P$3") (pinfunction "K2_P$3") (pintype "bidirectional"))
      (node (ref "R64") (pin "1") (pinfunction "1_1") (pintype "passive"))
    )
    (net (code "75") (name "L32") (class "Default")
      (node (ref "B17") (pin "P$2") (pinfunction "K1_P$2") (pintype "bidirectional"))
      (node (ref "B17ALT") (pin "P$2") (pinfunction "K1_P$2") (pintype "bidirectional"))
      (node (ref "R39") (pin "1") (pinfunction "1_1") (pintype "passive"))
    )
    (net (code "76") (name "L33") (class "Default")
      (node (ref "B17") (pin "P$3") (pinfunction "K2_P$3") (pintype "bidirectional"))
      (node (ref "B17ALT") (pin "P$3") (pinfunction "K2_P$3") (pintype "bidirectional"))
      (node (ref "R38") (pin "1") (pinfunction "1_1") (pintype "passive"))
    )
    (net (code "77") (name "L34") (class "Default")
      (node (ref "B18") (pin "P$2") (pinfunction "K1_P$2") (pintype "bidirectional"))
      (node (ref "B18ALT") (pin "P$2") (pinfunction "K1_P$2") (pintype "bidirectional"))
      (node (ref "R37") (pin "1") (pinfunction "1_1") (pintype "passive"))
    )
    (net (code "78") (name "L35") (class "Default")
      (node (ref "B18") (pin "P$3") (pinfunction "K2_P$3") (pintype "bidirectional"))
      (node (ref "B18ALT") (pin "P$3") (pinfunction "K2_P$3") (pintype "bidirectional"))
      (node (ref "R36") (pin "1") (pinfunction "1_1") (pintype "passive"))
    )
    (net (code "79") (name "L36") (class "Default")
      (node (ref "B19") (pin "P$2") (pinfunction "K1_P$2") (pintype "bidirectional"))
      (node (ref "B19ALT") (pin "P$2") (pinfunction "K1_P$2") (pintype "bidirectional"))
      (node (ref "R35") (pin "1") (pinfunction "1_1") (pintype "passive"))
    )
    (net (code "80") (name "L37") (class "Default")
      (node (ref "B19") (pin "P$3") (pinfunction "K2_P$3") (pintype "bidirectional"))
      (node (ref "B19ALT") (pin "P$3") (pinfunction "K2_P$3") (pintype "bidirectional"))
      (node (ref "R34") (pin "1") (pinfunction "1_1") (pintype "passive"))
    )
    (net (code "81") (name "L38") (class "Default")
      (node (ref "B20") (pin "P$2") (pinfunction "K1_P$2") (pintype "bidirectional"))
      (node (ref "B20ALT") (pin "P$2") (pinfunction "K1_P$2") (pintype "bidirectional"))
      (node (ref "R26") (pin "1") (pinfunction "1_1") (pintype "passive"))
    )
    (net (code "82") (name "L39") (class "Default")
      (node (ref "B20") (pin "P$3") (pinfunction "K2_P$3") (pintype "bidirectional"))
      (node (ref "B20ALT") (pin "P$3") (pinfunction "K2_P$3") (pintype "bidirectional"))
      (node (ref "R25") (pin "1") (pinfunction "1_1") (pintype "passive"))
    )
    (net (code "83") (name "L40") (class "Default")
      (node (ref "B21") (pin "P$2") (pinfunction "K1_P$2") (pintype "bidirectional"))
      (node (ref "R24") (pin "1") (pinfunction "1_1") (pintype "passive"))
    )
    (net (code "84") (name "L41") (class "Default")
      (node (ref "B21") (pin "P$3") (pinfunction "K2_P$3") (pintype "bidirectional"))
      (node (ref "R23") (pin "1") (pinfunction "1_1") (pintype "passive"))
    )
    (net (code "85") (name "L42") (class "Default")
      (node (ref "B22") (pin "P$2") (pinfunction "K1_P$2") (pintype "bidirectional"))
      (node (ref "R22") (pin "1") (pinfunction "1_1") (pintype "passive"))
    )
    (net (code "86") (name "L43") (class "Default")
      (node (ref "B22") (pin "P$3") (pinfunction "K2_P$3") (pintype "bidirectional"))
      (node (ref "R21") (pin "1") (pinfunction "1_1") (pintype "passive"))
    )
    (net (code "87") (name "L44") (class "Default")
      (node (ref "B23") (pin "P$2") (pinfunction "K1_P$2") (pintype "bidirectional"))
      (node (ref "B23ALT") (pin "P$2") (pinfunction "K1_P$2") (pintype "bidirectional"))
      (node (ref "R4") (pin "1") (pinfunction "1_1") (pintype "passive"))
    )
    (net (code "88") (name "L45") (class "Default")
      (node (ref "B23") (pin "P$3") (pinfunction "K2_P$3") (pintype "bidirectional"))
      (node (ref "B23ALT") (pin "P$3") (pinfunction "K2_P$3") (pintype "bidirectional"))
      (node (ref "R3") (pin "1") (pinfunction "1_1") (pintype "passive"))
    )
    (net (code "89") (name "L46") (class "Default")
      (node (ref "B24") (pin "P$2") (pinfunction "K1_P$2") (pintype "bidirectional"))
      (node (ref "B24ALT") (pin "P$2") (pinfunction "K1_P$2") (pintype "bidirectional"))
      (node (ref "R2") (pin "1") (pinfunction "1_1") (pintype "passive"))
    )
    (net (code "90") (name "L47") (class "Default")
      (node (ref "B24") (pin "P$3") (pinfunction "K2_P$3") (pintype "bidirectional"))
      (node (ref "B24ALT") (pin "P$3") (pinfunction "K2_P$3") (pintype "bidirectional"))
      (node (ref "R1") (pin "1") (pinfunction "1_1") (pintype "passive"))
    )
    (net (code "91") (name "L48") (class "Default")
      (node (ref "B25") (pin "P$2") (pinfunction "K1_P$2") (pintype "bidirectional"))
      (node (ref "B25ALT") (pin "P$2") (pinfunction "K1_P$2") (pintype "bidirectional"))
      (node (ref "R55") (pin "1") (pinfunction "1_1") (pintype "passive"))
    )
    (net (code "92") (name "L49") (class "Default")
      (node (ref "B25") (pin "P$3") (pinfunction "K2_P$3") (pintype "bidirectional"))
      (node (ref "B25ALT") (pin "P$3") (pinfunction "K2_P$3") (pintype "bidirectional"))
      (node (ref "R54") (pin "1") (pinfunction "1_1") (pintype "passive"))
    )
    (net (code "93") (name "L50") (class "Default")
      (node (ref "B26") (pin "P$2") (pinfunction "K1_P$2") (pintype "bidirectional"))
      (node (ref "B26ALT") (pin "P$2") (pinfunction "K1_P$2") (pintype "bidirectional"))
      (node (ref "R53") (pin "1") (pinfunction "1_1") (pintype "passive"))
    )
    (net (code "94") (name "L51") (class "Default")
      (node (ref "B26") (pin "P$3") (pinfunction "K2_P$3") (pintype "bidirectional"))
      (node (ref "B26ALT") (pin "P$3") (pinfunction "K2_P$3") (pintype "bidirectional"))
      (node (ref "R52") (pin "1") (pinfunction "1_1") (pintype "passive"))
    )
    (net (code "95") (name "L52") (class "Default")
      (node (ref "B27") (pin "P$2") (pinfunction "K1_P$2") (pintype "bidirectional"))
      (node (ref "B27ALT") (pin "P$2") (pinfunction "K1_P$2") (pintype "bidirectional"))
      (node (ref "R51") (pin "1") (pinfunction "1_1") (pintype "passive"))
    )
    (net (code "96") (name "L53") (class "Default")
      (node (ref "B27") (pin "P$3") (pinfunction "K2_P$3") (pintype "bidirectional"))
      (node (ref "B27ALT") (pin "P$3") (pinfunction "K2_P$3") (pintype "bidirectional"))
      (node (ref "R50") (pin "1") (pinfunction "1_1") (pintype "passive"))
    )
    (net (code "97") (name "L54") (class "Default")
      (node (ref "B28") (pin "P$2") (pinfunction "K1_P$2") (pintype "bidirectional"))
      (node (ref "B28ALT") (pin "P$2") (pinfunction "K1_P$2") (pintype "bidirectional"))
      (node (ref "R49") (pin "1") (pinfunction "1_1") (pintype "passive"))
    )
    (net (code "98") (name "L55") (class "Default")
      (node (ref "B28") (pin "P$3") (pinfunction "K2_P$3") (pintype "bidirectional"))
      (node (ref "B28ALT") (pin "P$3") (pinfunction "K2_P$3") (pintype "bidirectional"))
      (node (ref "R48") (pin "1") (pinfunction "1_1") (pintype "passive"))
    )
    (net (code "99") (name "L56") (class "Default")
      (node (ref "B29") (pin "P$2") (pinfunction "K1_P$2") (pintype "bidirectional"))
      (node (ref "B29ALT") (pin "P$2") (pinfunction "K1_P$2") (pintype "bidirectional"))
      (node (ref "R47") (pin "1") (pinfunction "1_1") (pintype "passive"))
    )
    (net (code "100") (name "L57") (class "Default")
      (node (ref "B29") (pin "P$3") (pinfunction "K2_P$3") (pintype "bidirectional"))
      (node (ref "B29ALT") (pin "P$3") (pinfunction "K2_P$3") (pintype "bidirectional"))
      (node (ref "R46") (pin "1") (pinfunction "1_1") (pintype "passive"))
    )
    (net (code "101") (name "L58") (class "Default")
      (node (ref "B30") (pin "P$2") (pinfunction "K1_P$2") (pintype "bidirectional"))
      (node (ref "B30ALT") (pin "P$2") (pinfunction "K1_P$2") (pintype "bidirectional"))
      (node (ref "R45") (pin "1") (pinfunction "1_1") (pintype "passive"))
    )
    (net (code "102") (name "L59") (class "Default")
      (node (ref "B30") (pin "P$3") (pinfunction "K2_P$3") (pintype "bidirectional"))
      (node (ref "B30ALT") (pin "P$3") (pinfunction "K2_P$3") (pintype "bidirectional"))
      (node (ref "R44") (pin "1") (pinfunction "1_1") (pintype "passive"))
    )
    (net (code "103") (name "L60") (class "Default")
      (node (ref "B31") (pin "P$2") (pinfunction "K1_P$2") (pintype "bidirectional"))
      (node (ref "B31ALT") (pin "P$2") (pinfunction "K1_P$2") (pintype "bidirectional"))
      (node (ref "R43") (pin "1") (pinfunction "1_1") (pintype "passive"))
    )
    (net (code "104") (name "L61") (class "Default")
      (node (ref "B31") (pin "P$3") (pinfunction "K2_P$3") (pintype "bidirectional"))
      (node (ref "B31ALT") (pin "P$3") (pinfunction "K2_P$3") (pintype "bidirectional"))
      (node (ref "R42") (pin "1") (pinfunction "1_1") (pintype "passive"))
    )
    (net (code "105") (name "L62") (class "Default")
      (node (ref "B32") (pin "P$2") (pinfunction "K1_P$2") (pintype "bidirectional"))
      (node (ref "B32ALT") (pin "P$2") (pinfunction "K1_P$2") (pintype "bidirectional"))
      (node (ref "R41") (pin "1") (pinfunction "1_1") (pintype "passive"))
    )
    (net (code "106") (name "L63") (class "Default")
      (node (ref "B32") (pin "P$3") (pinfunction "K2_P$3") (pintype "bidirectional"))
      (node (ref "B32ALT") (pin "P$3") (pinfunction "K2_P$3") (pintype "bidirectional"))
      (node (ref "R40") (pin "1") (pinfunction "1_1") (pintype "passive"))
    )
    (net (code "107") (name "MOSI") (class "Default")
      (node (ref "SERIAL") (pin "8") (pinfunction "8_8") (pintype "passive"))
      (node (ref "SSW1") (pin "6") (pinfunction "SDI_6") (pintype "bidirectional"))
      (node (ref "U$94") (pin "P$8") (pinfunction "8_P$8") (pintype "passive"))
    )
    (net (code "108") (name "Net-(IC2-L0)") (class "Default")
      (node (ref "IC2") (pin "6") (pinfunction "L0_6") (pintype "output"))
      (node (ref "R20") (pin "2") (pinfunction "2_2") (pintype "passive"))
    )
    (net (code "109") (name "Net-(IC2-L1)") (class "Default")
      (node (ref "IC2") (pin "7") (pinfunction "L1_7") (pintype "output"))
      (node (ref "R19") (pin "2") (pinfunction "2_2") (pintype "passive"))
    )
    (net (code "110") (name "Net-(IC2-L2)") (class "Default")
      (node (ref "IC2") (pin "8") (pinfunction "L2_8") (pintype "output"))
      (node (ref "R18") (pin "2") (pinfunction "2_2") (pintype "passive"))
    )
    (net (code "111") (name "Net-(IC2-L3)") (class "Default")
      (node (ref "IC2") (pin "9") (pinfunction "L3_9") (pintype "output"))
      (node (ref "R17") (pin "2") (pinfunction "2_2") (pintype "passive"))
    )
    (net (code "112") (name "Net-(IC2-L4)") (class "Default")
      (node (ref "IC2") (pin "10") (pinfunction "L4_10") (pintype "output"))
      (node (ref "R16") (pin "2") (pinfunction "2_2") (pintype "passive"))
    )
    (net (code "113") (name "Net-(IC2-L5)") (class "Default")
      (node (ref "IC2") (pin "11") (pinfunction "L5_11") (pintype "output"))
      (node (ref "R15") (pin "2") (pinfunction "2_2") (pintype "passive"))
    )
    (net (code "114") (name "Net-(IC2-L6)") (class "Default")
      (node (ref "IC2") (pin "12") (pinfunction "L6_12") (pintype "output"))
      (node (ref "R14") (pin "2") (pinfunction "2_2") (pintype "passive"))
    )
    (net (code "115") (name "Net-(IC2-L7)") (class "Default")
      (node (ref "IC2") (pin "13") (pinfunction "L7_13") (pintype "output"))
      (node (ref "R13") (pin "2") (pinfunction "2_2") (pintype "passive"))
    )
    (net (code "116") (name "Net-(IC2-L8)") (class "Default")
      (node (ref "IC2") (pin "15") (pinfunction "L8_15") (pintype "output"))
      (node (ref "R12") (pin "2") (pinfunction "2_2") (pintype "passive"))
    )
    (net (code "117") (name "Net-(IC2-L9)") (class "Default")
      (node (ref "IC2") (pin "16") (pinfunction "L9_16") (pintype "output"))
      (node (ref "R11") (pin "2") (pinfunction "2_2") (pintype "passive"))
    )
    (net (code "118") (name "Net-(IC2-L10)") (class "Default")
      (node (ref "IC2") (pin "17") (pinfunction "L10_17") (pintype "output"))
      (node (ref "R10") (pin "2") (pinfunction "2_2") (pintype "passive"))
    )
    (net (code "119") (name "Net-(IC2-L11)") (class "Default")
      (node (ref "IC2") (pin "18") (pinfunction "L11_18") (pintype "output"))
      (node (ref "R9") (pin "2") (pinfunction "2_2") (pintype "passive"))
    )
    (net (code "120") (name "Net-(IC2-L12)") (class "Default")
      (node (ref "IC2") (pin "19") (pinfunction "L12_19") (pintype "output"))
      (node (ref "R8") (pin "2") (pinfunction "2_2") (pintype "passive"))
    )
    (net (code "121") (name "Net-(IC2-L13)") (class "Default")
      (node (ref "IC2") (pin "20") (pinfunction "L13_20") (pintype "output"))
      (node (ref "R7") (pin "2") (pinfunction "2_2") (pintype "passive"))
    )
    (net (code "122") (name "Net-(IC2-L14)") (class "Default")
      (node (ref "IC2") (pin "21") (pinfunction "L14_21") (pintype "output"))
      (node (ref "R6") (pin "2") (pinfunction "2_2") (pintype "passive"))
    )
    (net (code "123") (name "Net-(IC2-L15)") (class "Default")
      (node (ref "IC2") (pin "22") (pinfunction "L15_22") (pintype "output"))
      (node (ref "R5") (pin "2") (pinfunction "2_2") (pintype "passive"))
    )
    (net (code "124") (name "Net-(IC3-L0)") (class "Default")
      (node (ref "IC3") (pin "6") (pinfunction "L0_6") (pintype "output"))
      (node (ref "R32") (pin "2") (pinfunction "2_2") (pintype "passive"))
    )
    (net (code "125") (name "Net-(IC3-L1)") (class "Default")
      (node (ref "IC3") (pin "7") (pinfunction "L1_7") (pintype "output"))
      (node (ref "R31") (pin "2") (pinfunction "2_2") (pintype "passive"))
    )
    (net (code "126") (name "Net-(IC3-L2)") (class "Default")
      (node (ref "IC3") (pin "8") (pinfunction "L2_8") (pintype "output"))
      (node (ref "R30") (pin "2") (pinfunction "2_2") (pintype "passive"))
    )
    (net (code "127") (name "Net-(IC3-L3)") (class "Default")
      (node (ref "IC3") (pin "9") (pinfunction "L3_9") (pintype "output"))
      (node (ref "R29") (pin "2") (pinfunction "2_2") (pintype "passive"))
    )
    (net (code "128") (name "Net-(IC3-L4)") (class "Default")
      (node (ref "IC3") (pin "10") (pinfunction "L4_10") (pintype "output"))
      (node (ref "R28") (pin "2") (pinfunction "2_2") (pintype "passive"))
    )
    (net (code "129") (name "Net-(IC3-L5)") (class "Default")
      (node (ref "IC3") (pin "11") (pinfunction "L5_11") (pintype "output"))
      (node (ref "R27") (pin "2") (pinfunction "2_2") (pintype "passive"))
    )
    (net (code "130") (name "Net-(IC3-L6)") (class "Default")
      (node (ref "IC3") (pin "12") (pinfunction "L6_12") (pintype "output"))
      (node (ref "R57") (pin "2") (pinfunction "2_2") (pintype "passive"))
    )
    (net (code "131") (name "Net-(IC3-L7)") (class "Default")
      (node (ref "IC3") (pin "13") (pinfunction "L7_13") (pintype "output"))
      (node (ref "R56") (pin "2") (pinfunction "2_2") (pintype "passive"))
    )
    (net (code "132") (name "Net-(IC3-L8)") (class "Default")
      (node (ref "IC3") (pin "15") (pinfunction "L8_15") (pintype "output"))
      (node (ref "R63") (pin "2") (pinfunction "2_2") (pintype "passive"))
    )
    (net (code "133") (name "Net-(IC3-L9)") (class "Default")
      (node (ref "IC3") (pin "16") (pinfunction "L9_16") (pintype "output"))
      (node (ref "R62") (pin "2") (pinfunction "2_2") (pintype "passive"))
    )
    (net (code "134") (name "Net-(IC3-L10)") (class "Default")
      (node (ref "IC3") (pin "17") (pinfunction "L10_17") (pintype "output"))
      (node (ref "R61") (pin "2") (pinfunction "2_2") (pintype "passive"))
    )
    (net (code "135") (name "Net-(IC3-L11)") (class "Default")
      (node (ref "IC3") (pin "18") (pinfunction "L11_18") (pintype "output"))
      (node (ref "R60") (pin "2") (pinfunction "2_2") (pintype "passive"))
    )
    (net (code "136") (name "Net-(IC3-L12)") (class "Default")
      (node (ref "IC3") (pin "19") (pinfunction "L12_19") (pintype "output"))
      (node (ref "R59") (pin "2") (pinfunction "2_2") (pintype "passive"))
    )
    (net (code "137") (name "Net-(IC3-L13)") (class "Default")
      (node (ref "IC3") (pin "20") (pinfunction "L13_20") (pintype "output"))
      (node (ref "R58") (pin "2") (pinfunction "2_2") (pintype "passive"))
    )
    (net (code "138") (name "Net-(IC3-L14)") (class "Default")
      (node (ref "IC3") (pin "21") (pinfunction "L14_21") (pintype "output"))
      (node (ref "R65") (pin "2") (pinfunction "2_2") (pintype "passive"))
    )
    (net (code "139") (name "Net-(IC3-L15)") (class "Default")
      (node (ref "IC3") (pin "22") (pinfunction "L15_22") (pintype "output"))
      (node (ref "R64") (pin "2") (pinfunction "2_2") (pintype "passive"))
    )
    (net (code "140") (name "Net-(IC5A-I)") (class "Default")
      (node (ref "C10") (pin "1") (pinfunction "1_1") (pintype "passive"))
      (node (ref "IC5") (pin "13") (pinfunction "I_13") (pintype "input"))
      (node (ref "R33") (pin "1") (pinfunction "1_1") (pintype "passive"))
      (node (ref "SW1") (pin "B") (pinfunction "B_B") (pintype "passive"))
    )
    (net (code "141") (name "Net-(IC6-L0)") (class "Default")
      (node (ref "IC6") (pin "6") (pinfunction "L0_6") (pintype "output"))
      (node (ref "R39") (pin "2") (pinfunction "2_2") (pintype "passive"))
    )
    (net (code "142") (name "Net-(IC6-L1)") (class "Default")
      (node (ref "IC6") (pin "7") (pinfunction "L1_7") (pintype "output"))
      (node (ref "R38") (pin "2") (pinfunction "2_2") (pintype "passive"))
    )
    (net (code "143") (name "Net-(IC6-L2)") (class "Default")
      (node (ref "IC6") (pin "8") (pinfunction "L2_8") (pintype "output"))
      (node (ref "R37") (pin "2") (pinfunction "2_2") (pintype "passive"))
    )
    (net (code "144") (name "Net-(IC6-L3)") (class "Default")
      (node (ref "IC6") (pin "9") (pinfunction "L3_9") (pintype "output"))
      (node (ref "R36") (pin "2") (pinfunction "2_2") (pintype "passive"))
    )
    (net (code "145") (name "Net-(IC6-L4)") (class "Default")
      (node (ref "IC6") (pin "10") (pinfunction "L4_10") (pintype "output"))
      (node (ref "R35") (pin "2") (pinfunction "2_2") (pintype "passive"))
    )
    (net (code "146") (name "Net-(IC6-L5)") (class "Default")
      (node (ref "IC6") (pin "11") (pinfunction "L5_11") (pintype "output"))
      (node (ref "R34") (pin "2") (pinfunction "2_2") (pintype "passive"))
    )
    (net (code "147") (name "Net-(IC6-L6)") (class "Default")
      (node (ref "IC6") (pin "12") (pinfunction "L6_12") (pintype "output"))
      (node (ref "R26") (pin "2") (pinfunction "2_2") (pintype "passive"))
    )
    (net (code "148") (name "Net-(IC6-L7)") (class "Default")
      (node (ref "IC6") (pin "13") (pinfunction "L7_13") (pintype "output"))
      (node (ref "R25") (pin "2") (pinfunction "2_2") (pintype "passive"))
    )
    (net (code "149") (name "Net-(IC6-L8)") (class "Default")
      (node (ref "IC6") (pin "15") (pinfunction "L8_15") (pintype "output"))
      (node (ref "R24") (pin "2") (pinfunction "2_2") (pintype "passive"))
    )
    (net (code "150") (name "Net-(IC6-L9)") (class "Default")
      (node (ref "IC6") (pin "16") (pinfunction "L9_16") (pintype "output"))
      (node (ref "R23") (pin "2") (pinfunction "2_2") (pintype "passive"))
    )
    (net (code "151") (name "Net-(IC6-L10)") (class "Default")
      (node (ref "IC6") (pin "17") (pinfunction "L10_17") (pintype "output"))
      (node (ref "R22") (pin "2") (pinfunction "2_2") (pintype "passive"))
    )
    (net (code "152") (name "Net-(IC6-L11)") (class "Default")
      (node (ref "IC6") (pin "18") (pinfunction "L11_18") (pintype "output"))
      (node (ref "R21") (pin "2") (pinfunction "2_2") (pintype "passive"))
    )
    (net (code "153") (name "Net-(IC6-L12)") (class "Default")
      (node (ref "IC6") (pin "19") (pinfunction "L12_19") (pintype "output"))
      (node (ref "R4") (pin "2") (pinfunction "2_2") (pintype "passive"))
    )
    (net (code "154") (name "Net-(IC6-L13)") (class "Default")
      (node (ref "IC6") (pin "20") (pinfunction "L13_20") (pintype "output"))
      (node (ref "R3") (pin "2") (pinfunction "2_2") (pintype "passive"))
    )
    (net (code "155") (name "Net-(IC6-L14)") (class "Default")
      (node (ref "IC6") (pin "21") (pinfunction "L14_21") (pintype "output"))
      (node (ref "R2") (pin "2") (pinfunction "2_2") (pintype "passive"))
    )
    (net (code "156") (name "Net-(IC6-L15)") (class "Default")
      (node (ref "IC6") (pin "22") (pinfunction "L15_22") (pintype "output"))
      (node (ref "R1") (pin "2") (pinfunction "2_2") (pintype "passive"))
    )
    (net (code "157") (name "Net-(IC8-L0)") (class "Default")
      (node (ref "IC8") (pin "6") (pinfunction "L0_6") (pintype "output"))
      (node (ref "R55") (pin "2") (pinfunction "2_2") (pintype "passive"))
    )
    (net (code "158") (name "Net-(IC8-L1)") (class "Default")
      (node (ref "IC8") (pin "7") (pinfunction "L1_7") (pintype "output"))
      (node (ref "R54") (pin "2") (pinfunction "2_2") (pintype "passive"))
    )
    (net (code "159") (name "Net-(IC8-L2)") (class "Default")
      (node (ref "IC8") (pin "8") (pinfunction "L2_8") (pintype "output"))
      (node (ref "R53") (pin "2") (pinfunction "2_2") (pintype "passive"))
    )
    (net (code "160") (name "Net-(IC8-L3)") (class "Default")
      (node (ref "IC8") (pin "9") (pinfunction "L3_9") (pintype "output"))
      (node (ref "R52") (pin "2") (pinfunction "2_2") (pintype "passive"))
    )
    (net (code "161") (name "Net-(IC8-L4)") (class "Default")
      (node (ref "IC8") (pin "10") (pinfunction "L4_10") (pintype "output"))
      (node (ref "R51") (pin "2") (pinfunction "2_2") (pintype "passive"))
    )
    (net (code "162") (name "Net-(IC8-L5)") (class "Default")
      (node (ref "IC8") (pin "11") (pinfunction "L5_11") (pintype "output"))
      (node (ref "R50") (pin "2") (pinfunction "2_2") (pintype "passive"))
    )
    (net (code "163") (name "Net-(IC8-L6)") (class "Default")
      (node (ref "IC8") (pin "12") (pinfunction "L6_12") (pintype "output"))
      (node (ref "R49") (pin "2") (pinfunction "2_2") (pintype "passive"))
    )
    (net (code "164") (name "Net-(IC8-L7)") (class "Default")
      (node (ref "IC8") (pin "13") (pinfunction "L7_13") (pintype "output"))
      (node (ref "R48") (pin "2") (pinfunction "2_2") (pintype "passive"))
    )
    (net (code "165") (name "Net-(IC8-L8)") (class "Default")
      (node (ref "IC8") (pin "15") (pinfunction "L8_15") (pintype "output"))
      (node (ref "R47") (pin "2") (pinfunction "2_2") (pintype "passive"))
    )
    (net (code "166") (name "Net-(IC8-L9)") (class "Default")
      (node (ref "IC8") (pin "16") (pinfunction "L9_16") (pintype "output"))
      (node (ref "R46") (pin "2") (pinfunction "2_2") (pintype "passive"))
    )
    (net (code "167") (name "Net-(IC8-L10)") (class "Default")
      (node (ref "IC8") (pin "17") (pinfunction "L10_17") (pintype "output"))
      (node (ref "R45") (pin "2") (pinfunction "2_2") (pintype "passive"))
    )
    (net (code "168") (name "Net-(IC8-L11)") (class "Default")
      (node (ref "IC8") (pin "18") (pinfunction "L11_18") (pintype "output"))
      (node (ref "R44") (pin "2") (pinfunction "2_2") (pintype "passive"))
    )
    (net (code "169") (name "Net-(IC8-L12)") (class "Default")
      (node (ref "IC8") (pin "19") (pinfunction "L12_19") (pintype "output"))
      (node (ref "R43") (pin "2") (pinfunction "2_2") (pintype "passive"))
    )
    (net (code "170") (name "Net-(IC8-L13)") (class "Default")
      (node (ref "IC8") (pin "20") (pinfunction "L13_20") (pintype "output"))
      (node (ref "R42") (pin "2") (pinfunction "2_2") (pintype "passive"))
    )
    (net (code "171") (name "Net-(IC8-L14)") (class "Default")
      (node (ref "IC8") (pin "21") (pinfunction "L14_21") (pintype "output"))
      (node (ref "R41") (pin "2") (pinfunction "2_2") (pintype "passive"))
    )
    (net (code "172") (name "Net-(IC8-L15)") (class "Default")
      (node (ref "IC8") (pin "22") (pinfunction "L15_22") (pintype "output"))
      (node (ref "R40") (pin "2") (pinfunction "2_2") (pintype "passive"))
    )
    (net (code "173") (name "SCLK") (class "Default")
      (node (ref "SERIAL") (pin "7") (pinfunction "7_7") (pintype "passive"))
      (node (ref "SSW1") (pin "7") (pinfunction "SCK_7") (pintype "bidirectional"))
      (node (ref "U$94") (pin "P$7") (pinfunction "7_P$7") (pintype "passive"))
    )
    (net (code "174") (name "unconnected-(IC1-INTA-Pad20)") (class "Default")
      (node (ref "IC1") (pin "20") (pinfunction "INTA_20") (pintype "output"))
    )
    (net (code "175") (name "unconnected-(IC1-INTB-Pad19)") (class "Default")
      (node (ref "IC1") (pin "19") (pinfunction "INTB_19") (pintype "output"))
    )
    (net (code "176") (name "unconnected-(IC4-GPA2-Pad23)") (class "Default")
      (node (ref "IC4") (pin "23") (pinfunction "GPA2_23") (pintype "bidirectional"))
    )
    (net (code "177") (name "unconnected-(IC4-GPA3-Pad24)") (class "Default")
      (node (ref "IC4") (pin "24") (pinfunction "GPA3_24") (pintype "bidirectional"))
    )
    (net (code "178") (name "unconnected-(IC4-GPA5-Pad26)") (class "Default")
      (node (ref "IC4") (pin "26") (pinfunction "GPA5_26") (pintype "bidirectional"))
    )
    (net (code "179") (name "unconnected-(IC4-GPA6-Pad27)") (class "Default")
      (node (ref "IC4") (pin "27") (pinfunction "GPA6_27") (pintype "bidirectional"))
    )
    (net (code "180") (name "unconnected-(IC4-GPA7-Pad28)") (class "Default")
      (node (ref "IC4") (pin "28") (pinfunction "GPA7_28") (pintype "bidirectional"))
    )
    (net (code "181") (name "unconnected-(IC4-GPB1-Pad2)") (class "Default")
      (node (ref "IC4") (pin "2") (pinfunction "GPB1_2") (pintype "bidirectional"))
    )
    (net (code "182") (name "unconnected-(IC4-GPB2-Pad3)") (class "Default")
      (node (ref "IC4") (pin "3") (pinfunction "GPB2_3") (pintype "bidirectional"))
    )
    (net (code "183") (name "unconnected-(IC4-GPB3-Pad4)") (class "Default")
      (node (ref "IC4") (pin "4") (pinfunction "GPB3_4") (pintype "bidirectional"))
    )
    (net (code "184") (name "unconnected-(IC4-GPB5-Pad6)") (class "Default")
      (node (ref "IC4") (pin "6") (pinfunction "GPB5_6") (pintype "bidirectional"))
    )
    (net (code "185") (name "unconnected-(IC4-GPB6-Pad7)") (class "Default")
      (node (ref "IC4") (pin "7") (pinfunction "GPB6_7") (pintype "bidirectional"))
    )
    (net (code "186") (name "unconnected-(IC4-GPB7-Pad8)") (class "Default")
      (node (ref "IC4") (pin "8") (pinfunction "GPB7_8") (pintype "bidirectional"))
    )
    (net (code "187") (name "unconnected-(IC4-INTA-Pad20)") (class "Default")
      (node (ref "IC4") (pin "20") (pinfunction "INTA_20") (pintype "output"))
    )
    (net (code "188") (name "unconnected-(IC4-INTB-Pad19)") (class "Default")
      (node (ref "IC4") (pin "19") (pinfunction "INTB_19") (pintype "output"))
    )
    (net (code "189") (name "unconnected-(IC5B-O-Pad10)") (class "Default")
      (node (ref "IC5") (pin "10") (pinfunction "O_10") (pintype "output"))
    )
    (net (code "190") (name "unconnected-(IC5C-O-Pad8)") (class "Default")
      (node (ref "IC5") (pin "8") (pinfunction "O_8") (pintype "output"))
    )
    (net (code "191") (name "unconnected-(IC5D-O-Pad2)") (class "Default")
      (node (ref "IC5") (pin "2") (pinfunction "O_2") (pintype "output"))
    )
    (net (code "192") (name "unconnected-(IC5E-O-Pad4)") (class "Default")
      (node (ref "IC5") (pin "4") (pinfunction "O_4") (pintype "output"))
    )
    (net (code "193") (name "unconnected-(IC5F-O-Pad6)") (class "Default")
      (node (ref "IC5") (pin "6") (pinfunction "O_6") (pintype "output"))
    )
    (net (code "194") (name "unconnected-(IC7-INTA-Pad20)") (class "Default")
      (node (ref "IC7") (pin "20") (pinfunction "INTA_20") (pintype "output"))
    )
    (net (code "195") (name "unconnected-(IC7-INTB-Pad19)") (class "Default")
      (node (ref "IC7") (pin "19") (pinfunction "INTB_19") (pintype "output"))
    )
    (net (code "196") (name "unconnected-(SERIAL-Pad6)") (class "Default")
      (node (ref "SERIAL") (pin "6") (pinfunction "6_6") (pintype "passive"))
    )
    (net (code "197") (name "unconnected-(SSW1-SDO-Pad5)") (class "Default")
      (node (ref "SSW1") (pin "5") (pinfunction "SDO_5") (pintype "bidirectional"))
    )
    (net (code "198") (name "unconnected-(U$94-5-PadP$5)") (class "Default")
      (node (ref "U$94") (pin "P$5") (pinfunction "5_P$5") (pintype "passive"))
    )
    (net (code "199") (name "unconnected-(U$94-6-PadP$6)") (class "Default")
      (node (ref "U$94") (pin "P$6") (pinfunction "6_P$6") (pintype "passive"))
    )
  )
)
